# bontor_mbed_lowpan_rev_h.net
KiCad netlist of a schematic drawn in EAGLE
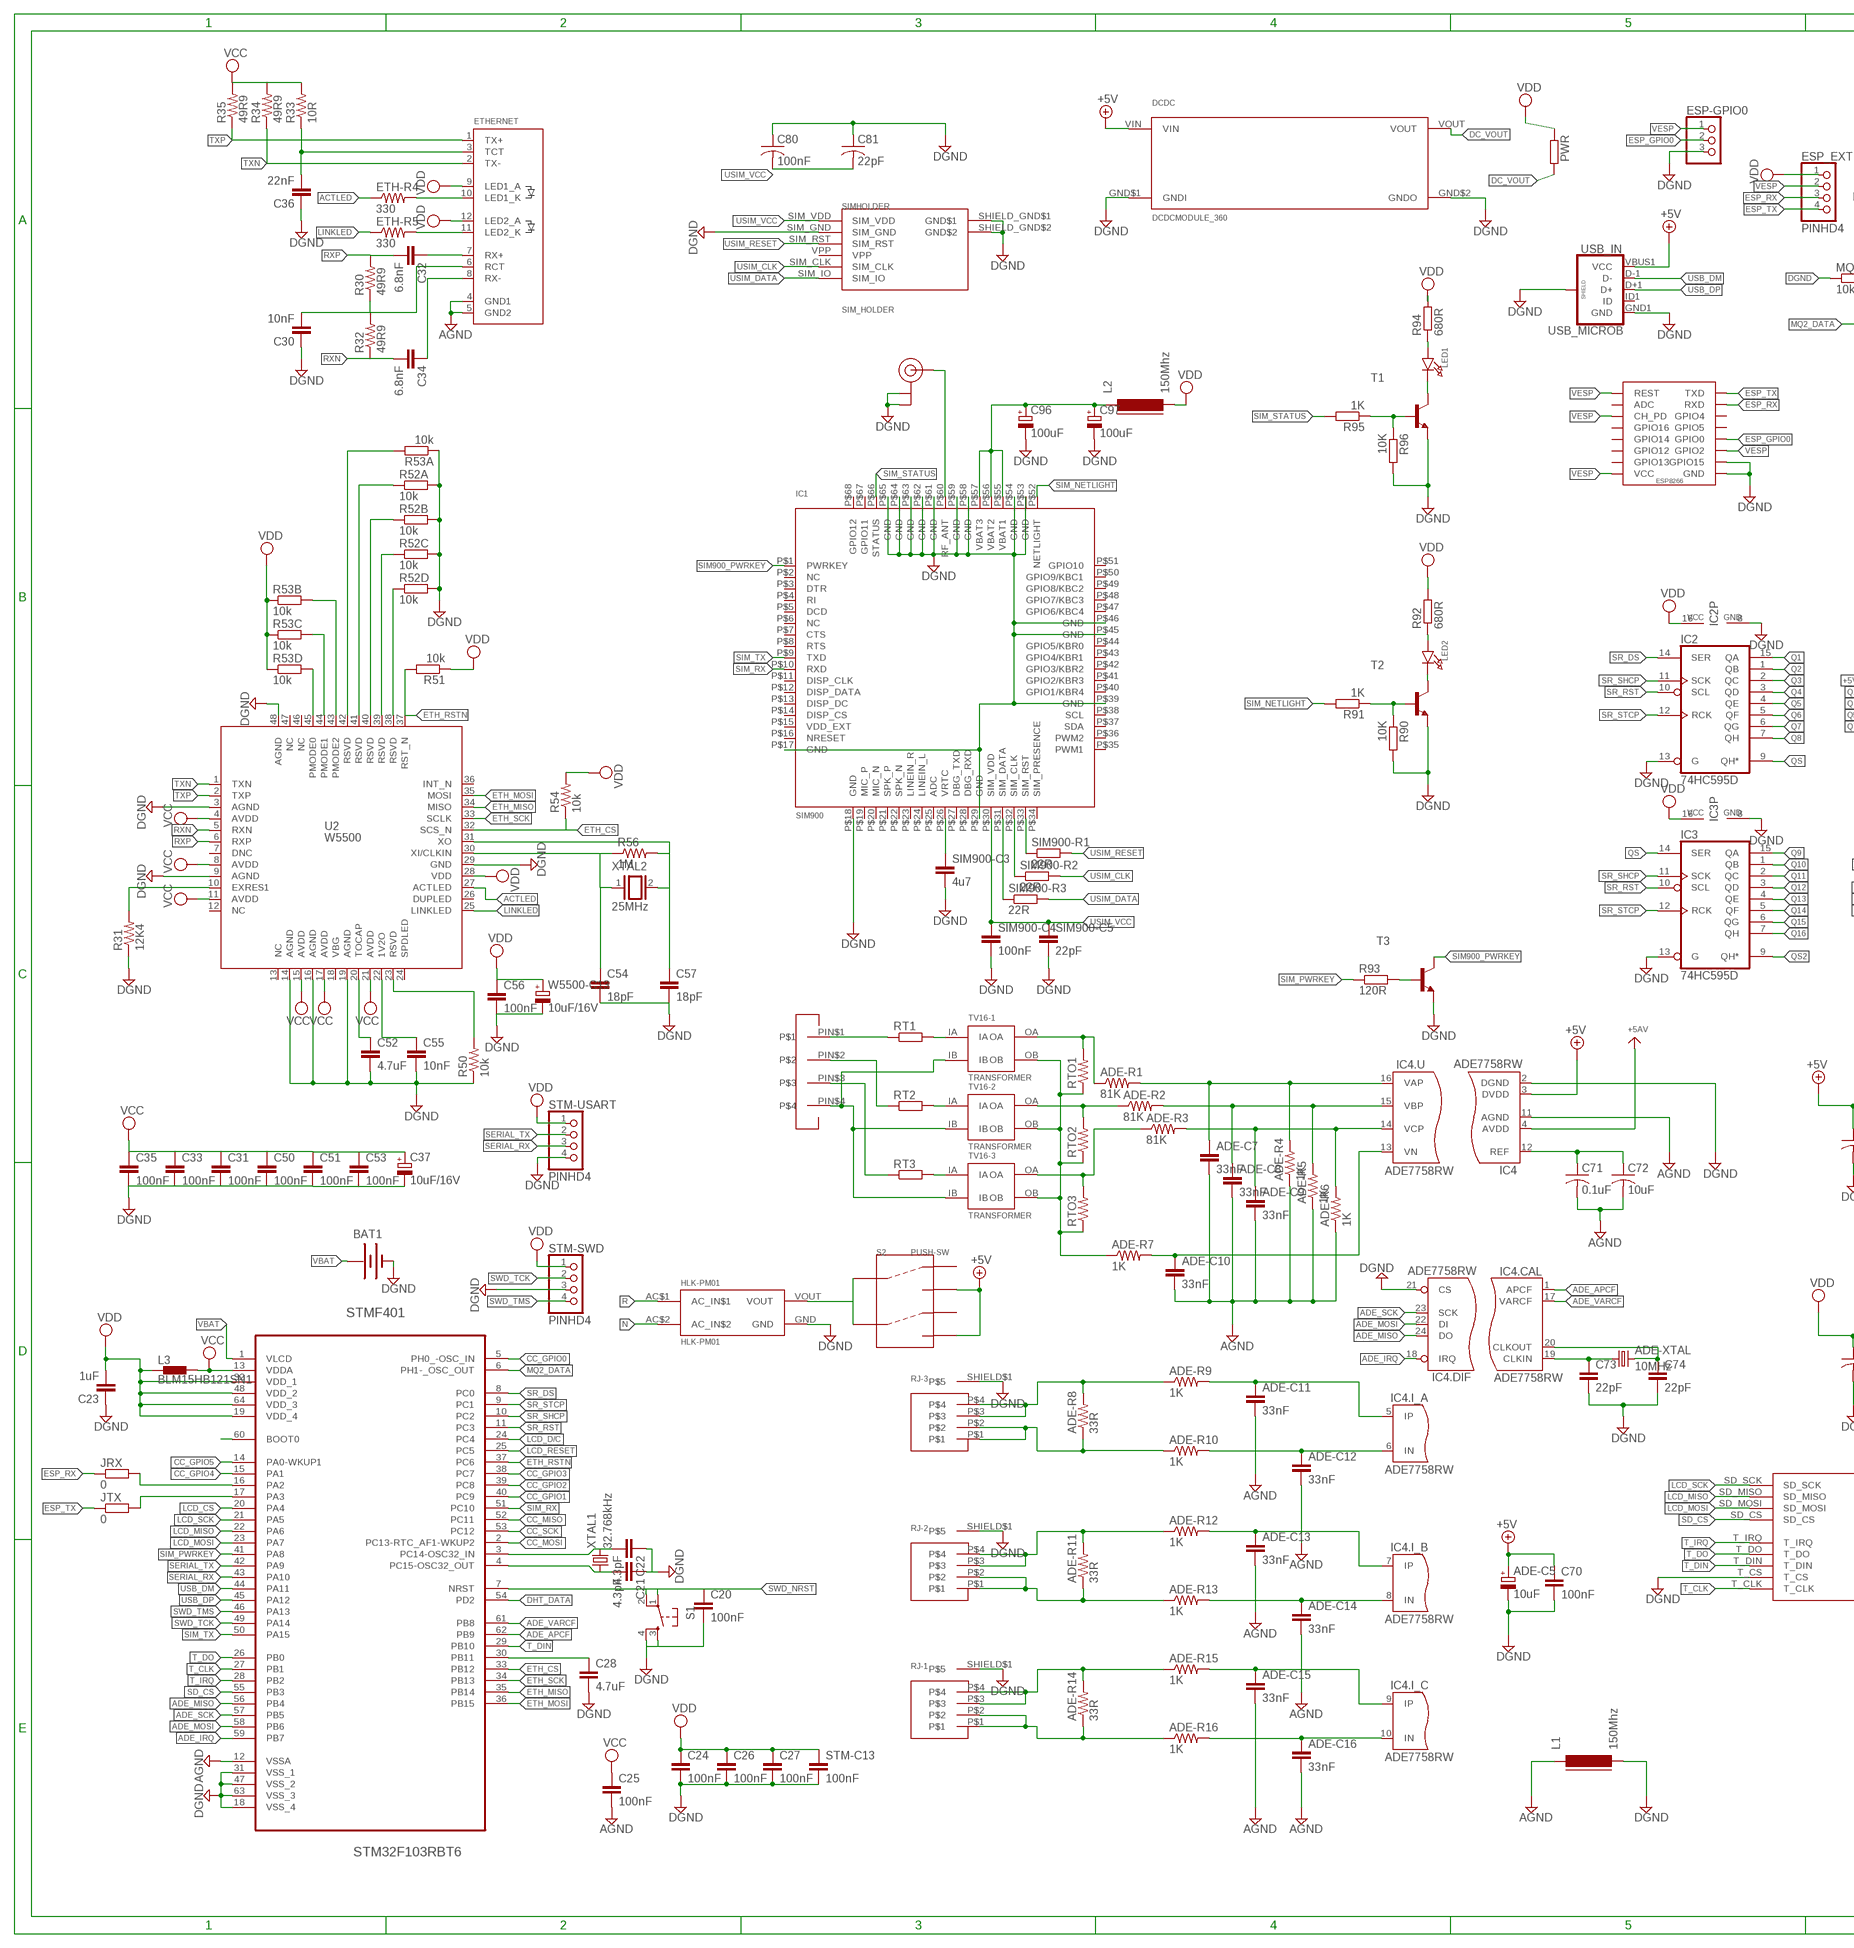
[diagram p0: schematic, sheet 1, part 1 of 2]
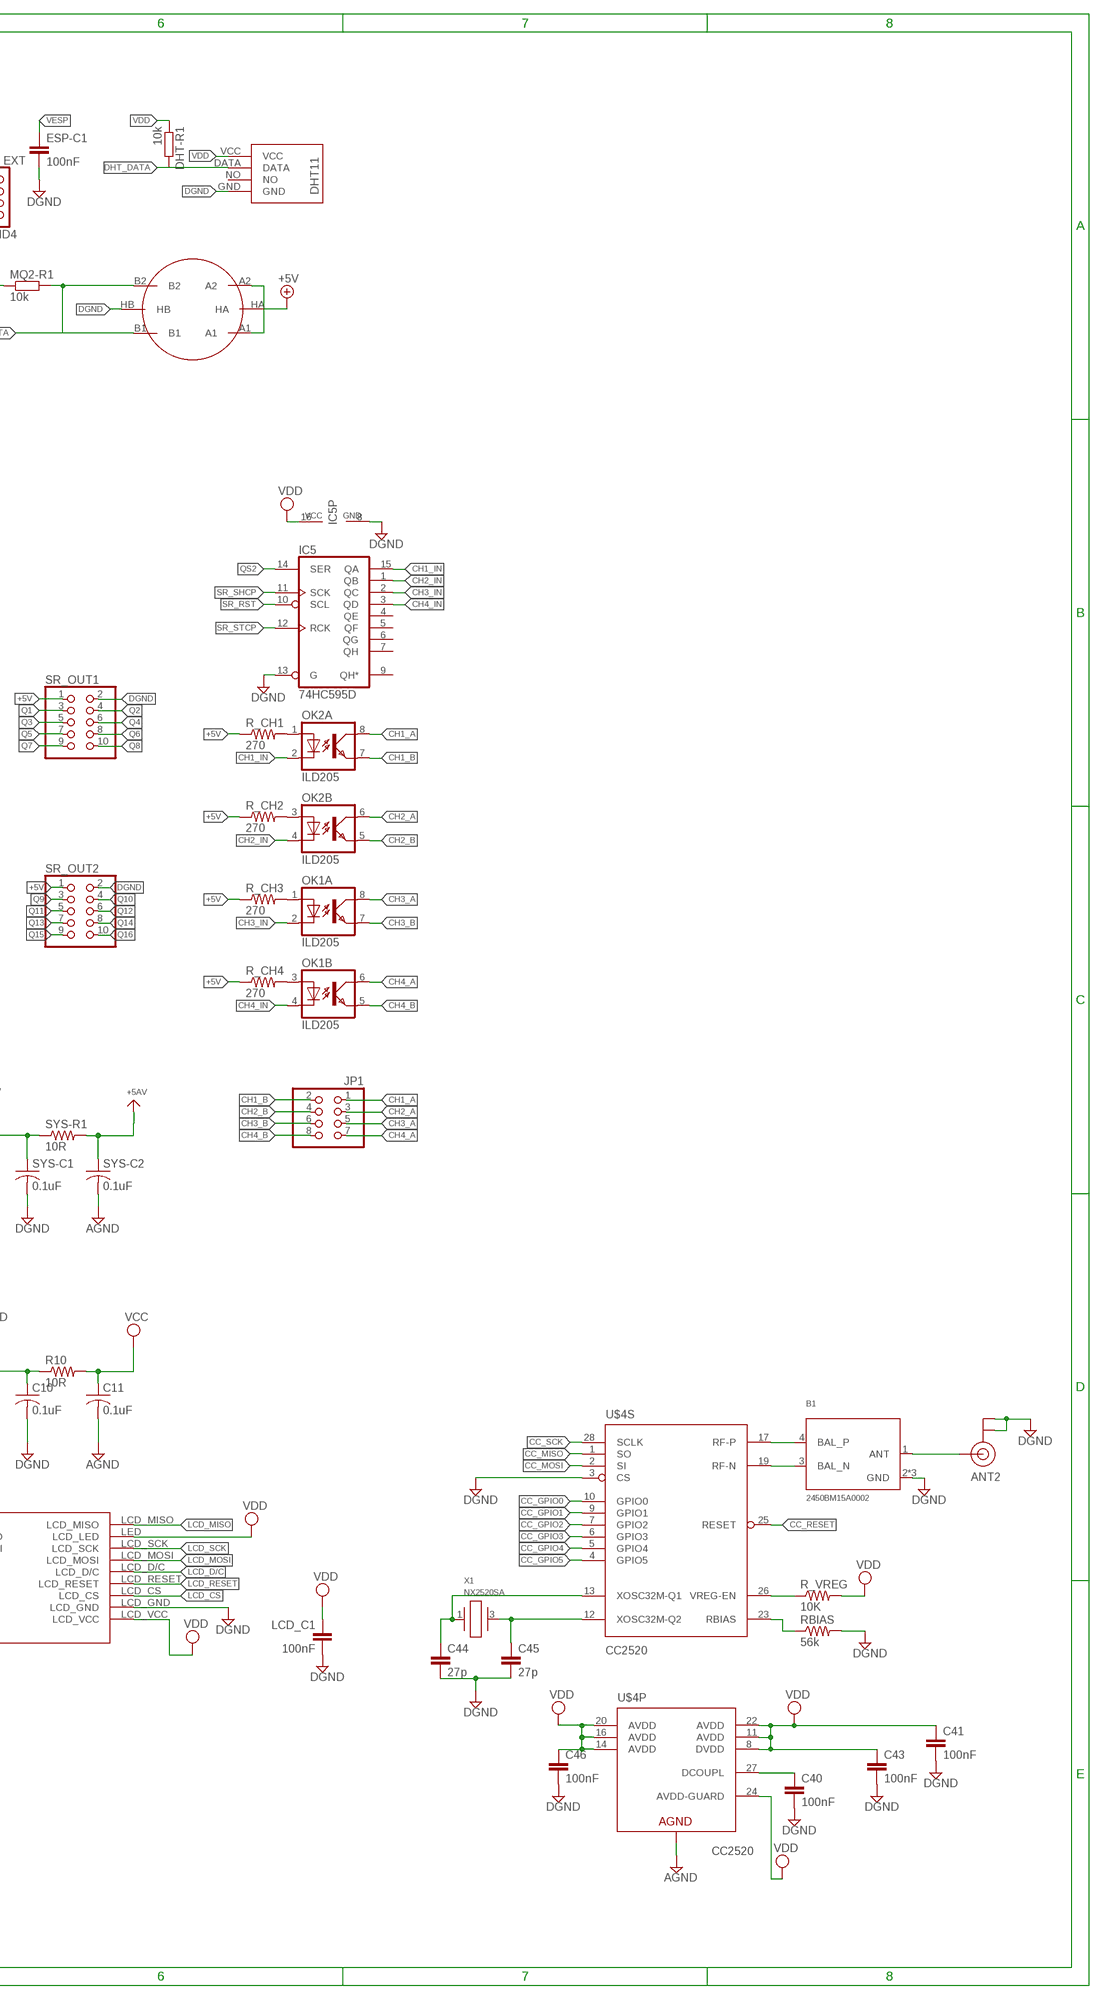
[diagram p1: schematic, sheet 1, part 2 of 2]

(export (version "E")
  (design (tool "Eeschema 10.0.6"))
  (components
    (comp (ref "ADE-C5")
      (value "10uF")
      (footprint "eagle-import:153CLV-0605")
      (libsource (lib "eagle-import") (part "CPOL-EU153CLV-0605"))
    )
    (comp (ref "ADE-C7")
      (value "33nF")
      (footprint "eagle-import:0603-CAP")
      (libsource (lib "eagle-import") (part "CAP0603-CAP"))
    )
    (comp (ref "ADE-C8")
      (value "33nF")
      (footprint "eagle-import:0603-CAP")
      (libsource (lib "eagle-import") (part "CAP0603-CAP"))
    )
    (comp (ref "ADE-C9")
      (value "33nF")
      (footprint "eagle-import:0603-CAP")
      (libsource (lib "eagle-import") (part "CAP0603-CAP"))
    )
    (comp (ref "ADE-C10")
      (value "33nF")
      (footprint "eagle-import:0603-CAP")
      (libsource (lib "eagle-import") (part "CAP0603-CAP"))
    )
    (comp (ref "ADE-C11")
      (value "33nF")
      (footprint "eagle-import:0402-CAP")
      (libsource (lib "eagle-import") (part "CAP0402-CAP"))
    )
    (comp (ref "ADE-C12")
      (value "33nF")
      (footprint "eagle-import:0402-CAP")
      (libsource (lib "eagle-import") (part "CAP0402-CAP"))
    )
    (comp (ref "ADE-C13")
      (value "33nF")
      (footprint "eagle-import:0402-CAP")
      (libsource (lib "eagle-import") (part "CAP0402-CAP"))
    )
    (comp (ref "ADE-C14")
      (value "33nF")
      (footprint "eagle-import:0402-CAP")
      (libsource (lib "eagle-import") (part "CAP0402-CAP"))
    )
    (comp (ref "ADE-C15")
      (value "33nF")
      (footprint "eagle-import:0402-CAP")
      (libsource (lib "eagle-import") (part "CAP0402-CAP"))
    )
    (comp (ref "ADE-C16")
      (value "33nF")
      (footprint "eagle-import:0402-CAP")
      (libsource (lib "eagle-import") (part "CAP0402-CAP"))
    )
    (comp (ref "ADE-R1")
      (value "81K")
      (footprint "eagle-import:0603-RES")
      (libsource (lib "eagle-import") (part "RESISTOR0603-RES"))
    )
    (comp (ref "ADE-R2")
      (value "81K")
      (footprint "eagle-import:0603-RES")
      (libsource (lib "eagle-import") (part "RESISTOR0603-RES"))
    )
    (comp (ref "ADE-R3")
      (value "81K")
      (footprint "eagle-import:0603-RES")
      (libsource (lib "eagle-import") (part "RESISTOR0603-RES"))
    )
    (comp (ref "ADE-R4")
      (value "1K")
      (footprint "eagle-import:0603-RES")
      (libsource (lib "eagle-import") (part "RESISTOR0603-RES"))
    )
    (comp (ref "ADE-R5")
      (value "1K")
      (footprint "eagle-import:0603-RES")
      (libsource (lib "eagle-import") (part "RESISTOR0603-RES"))
    )
    (comp (ref "ADE-R6")
      (value "1K")
      (footprint "eagle-import:0603-RES")
      (libsource (lib "eagle-import") (part "RESISTOR0603-RES"))
    )
    (comp (ref "ADE-R7")
      (value "1K")
      (footprint "eagle-import:0603-RES")
      (libsource (lib "eagle-import") (part "RESISTOR0603-RES"))
    )
    (comp (ref "ADE-R8")
      (value "33R")
      (footprint "eagle-import:0402-RES")
      (libsource (lib "eagle-import") (part "RESISTOR0402-RES"))
    )
    (comp (ref "ADE-R9")
      (value "1K")
      (footprint "eagle-import:0402-RES")
      (libsource (lib "eagle-import") (part "RESISTOR0402-RES"))
    )
    (comp (ref "ADE-R10")
      (value "1K")
      (footprint "eagle-import:0402-RES")
      (libsource (lib "eagle-import") (part "RESISTOR0402-RES"))
    )
    (comp (ref "ADE-R11")
      (value "33R")
      (footprint "eagle-import:0402-RES")
      (libsource (lib "eagle-import") (part "RESISTOR0402-RES"))
    )
    (comp (ref "ADE-R12")
      (value "1K")
      (footprint "eagle-import:0402-RES")
      (libsource (lib "eagle-import") (part "RESISTOR0402-RES"))
    )
    (comp (ref "ADE-R13")
      (value "1K")
      (footprint "eagle-import:0402-RES")
      (libsource (lib "eagle-import") (part "RESISTOR0402-RES"))
    )
    (comp (ref "ADE-R14")
      (value "33R")
      (footprint "eagle-import:0402-RES")
      (libsource (lib "eagle-import") (part "RESISTOR0402-RES"))
    )
    (comp (ref "ADE-R15")
      (value "1K")
      (footprint "eagle-import:0402-RES")
      (libsource (lib "eagle-import") (part "RESISTOR0402-RES"))
    )
    (comp (ref "ADE-R16")
      (value "1K")
      (footprint "eagle-import:0402-RES")
      (libsource (lib "eagle-import") (part "RESISTOR0402-RES"))
    )
    (comp (ref "ADE-XTAL")
      (value "10MHz")
      (footprint "eagle-import:HC49US")
      (libsource (lib "eagle-import") (part "CRYSTALHC49US"))
    )
    (comp (ref "ANT1")
      (value "U.FL")
      (footprint "eagle-import:U.FL")
      (libsource (lib "eagle-import") (part "U.FL"))
    )
    (comp (ref "ANT2")
      (value "U.FL")
      (footprint "eagle-import:U.FL")
      (libsource (lib "eagle-import") (part "SparkFun-Connectors_U.FL"))
    )
    (comp (ref "B1")
      (value "2450BM15A0002")
      (footprint "eagle-import:2450BM")
      (libsource (lib "eagle-import") (part "2450BM15A0002"))
    )
    (comp (ref "BAT1")
      (value "BATTERY12MM")
      (footprint "eagle-import:BATTCON_12MM")
      (libsource (lib "eagle-import") (part "BATTERY12MM"))
    )
    (comp (ref "C10")
      (value "0.1uF")
      (footprint "eagle-import:C0603")
      (libsource (lib "eagle-import") (part "C-USC0603"))
    )
    (comp (ref "C11")
      (value "0.1uF")
      (footprint "eagle-import:C0603")
      (libsource (lib "eagle-import") (part "C-USC0603"))
    )
    (comp (ref "C20")
      (value "100nF")
      (footprint "eagle-import:C0603")
      (libsource (lib "eagle-import") (part "C-EUC0603"))
    )
    (comp (ref "C21")
      (value "4.3pF")
      (footprint "eagle-import:C0603")
      (libsource (lib "eagle-import") (part "C-EUC0603"))
    )
    (comp (ref "C22")
      (value "4.3pF")
      (footprint "eagle-import:C0603")
      (libsource (lib "eagle-import") (part "C-EUC0603"))
    )
    (comp (ref "C23")
      (value "1uF")
      (footprint "eagle-import:C0603")
      (libsource (lib "eagle-import") (part "C-EUC0603"))
    )
    (comp (ref "C24")
      (value "100nF")
      (footprint "eagle-import:C0603")
      (libsource (lib "eagle-import") (part "C-EUC0603"))
    )
    (comp (ref "C25")
      (value "100nF")
      (footprint "eagle-import:C0603")
      (libsource (lib "eagle-import") (part "C-EUC0603"))
    )
    (comp (ref "C26")
      (value "100nF")
      (footprint "eagle-import:C0603")
      (libsource (lib "eagle-import") (part "C-EUC0603"))
    )
    (comp (ref "C27")
      (value "100nF")
      (footprint "eagle-import:C0402")
      (libsource (lib "eagle-import") (part "C-EUC0402"))
    )
    (comp (ref "C28")
      (value "4.7uF")
      (footprint "eagle-import:C0603")
      (libsource (lib "eagle-import") (part "C-EUC0603"))
    )
    (comp (ref "C30")
      (value "10nF")
      (footprint "eagle-import:C0603")
      (libsource (lib "eagle-import") (part "C-EUC0603"))
    )
    (comp (ref "C31")
      (value "100nF")
      (footprint "eagle-import:C0603")
      (libsource (lib "eagle-import") (part "C-EUC0603"))
    )
    (comp (ref "C32")
      (value "6.8nF")
      (footprint "eagle-import:C0603")
      (libsource (lib "eagle-import") (part "C-EUC0603"))
    )
    (comp (ref "C33")
      (value "100nF")
      (footprint "eagle-import:C0603")
      (libsource (lib "eagle-import") (part "C-EUC0603"))
    )
    (comp (ref "C34")
      (value "6.8nF")
      (footprint "eagle-import:C0603")
      (libsource (lib "eagle-import") (part "C-EUC0603"))
    )
    (comp (ref "C35")
      (value "100nF")
      (footprint "eagle-import:C0603")
      (libsource (lib "eagle-import") (part "C-EUC0603"))
    )
    (comp (ref "C36")
      (value "22nF")
      (footprint "eagle-import:C0603")
      (libsource (lib "eagle-import") (part "C-EUC0603"))
    )
    (comp (ref "C37")
      (value "10uF/16V")
      (footprint "eagle-import:153CLV-0605")
      (libsource (lib "eagle-import") (part "CPOL-EU153CLV-0605"))
    )
    (comp (ref "C40")
      (value "100nF")
      (footprint "eagle-import:C0402")
      (libsource (lib "eagle-import") (part "C-EUC0402"))
    )
    (comp (ref "C41")
      (value "100nF")
      (footprint "eagle-import:C0402")
      (libsource (lib "eagle-import") (part "C-EUC0402"))
    )
    (comp (ref "C43")
      (value "100nF")
      (footprint "eagle-import:C0402")
      (libsource (lib "eagle-import") (part "C-EUC0402"))
    )
    (comp (ref "C44")
      (value "27p")
      (footprint "eagle-import:C0201")
      (libsource (lib "eagle-import") (part "C-EUC0201"))
    )
    (comp (ref "C45")
      (value "27p")
      (footprint "eagle-import:C0201")
      (libsource (lib "eagle-import") (part "C-EUC0201"))
    )
    (comp (ref "C46")
      (value "100nF")
      (footprint "eagle-import:C0402")
      (libsource (lib "eagle-import") (part "C-EUC0402"))
    )
    (comp (ref "C50")
      (value "100nF")
      (footprint "eagle-import:C0603")
      (libsource (lib "eagle-import") (part "C-EUC0603"))
    )
    (comp (ref "C51")
      (value "100nF")
      (footprint "eagle-import:C0603")
      (libsource (lib "eagle-import") (part "C-EUC0603"))
    )
    (comp (ref "C52")
      (value "4.7uF")
      (footprint "eagle-import:C0603")
      (libsource (lib "eagle-import") (part "C-EUC0603"))
    )
    (comp (ref "C53")
      (value "100nF")
      (footprint "eagle-import:C0603")
      (libsource (lib "eagle-import") (part "C-EUC0603"))
    )
    (comp (ref "C54")
      (value "18pF")
      (footprint "eagle-import:C0603")
      (libsource (lib "eagle-import") (part "C-EUC0603"))
    )
    (comp (ref "C55")
      (value "10nF")
      (footprint "eagle-import:C0603")
      (libsource (lib "eagle-import") (part "C-EUC0603"))
    )
    (comp (ref "C56")
      (value "100nF")
      (footprint "eagle-import:C0603")
      (libsource (lib "eagle-import") (part "C-EUC0603"))
    )
    (comp (ref "C57")
      (value "18pF")
      (footprint "eagle-import:C0603")
      (libsource (lib "eagle-import") (part "C-EUC0603"))
    )
    (comp (ref "C70")
      (value "100nF")
      (footprint "eagle-import:C0603")
      (libsource (lib "eagle-import") (part "C-EUC0603"))
    )
    (comp (ref "C71")
      (value "0.1uF")
      (footprint "eagle-import:C0603")
      (libsource (lib "eagle-import") (part "C-USC0603"))
    )
    (comp (ref "C72")
      (value "10uF")
      (footprint "eagle-import:C0805K")
      (libsource (lib "eagle-import") (part "C-USC0805K"))
    )
    (comp (ref "C73")
      (value "22pF")
      (footprint "eagle-import:C0603")
      (libsource (lib "eagle-import") (part "C-EUC0603"))
    )
    (comp (ref "C74")
      (value "22pF")
      (footprint "eagle-import:C0603")
      (libsource (lib "eagle-import") (part "C-EUC0603"))
    )
    (comp (ref "C80")
      (value "100nF")
      (footprint "eagle-import:C0603K")
      (libsource (lib "eagle-import") (part "C-USC0603K"))
    )
    (comp (ref "C81")
      (value "22pF")
      (footprint "eagle-import:C0603K")
      (libsource (lib "eagle-import") (part "C-USC0603K"))
    )
    (comp (ref "C96")
      (value "100uF")
      (footprint "eagle-import:153CLV-0605")
      (libsource (lib "eagle-import") (part "CPOL-EU153CLV-0605"))
    )
    (comp (ref "C97")
      (value "100uF")
      (footprint "eagle-import:153CLV-0605")
      (libsource (lib "eagle-import") (part "CPOL-EU153CLV-0605"))
    )
    (comp (ref "DCDC")
      (value "DCDCMODULE_360")
      (footprint "eagle-import:DCDCMODULE-360")
      (libsource (lib "eagle-import") (part "DCDCMODULE_360"))
    )
    (comp (ref "DHT-R1")
      (value "10k")
      (footprint "eagle-import:R0603")
      (libsource (lib "eagle-import") (part "resistor_R-EU_R0603"))
    )
    (comp (ref "ESP")
      (value "ESP")
      (footprint "eagle-import:WI12")
      (libsource (lib "eagle-import") (part "ESP8266WI12"))
    )
    (comp (ref "ESP-C1")
      (value "100nF")
      (footprint "eagle-import:C0603")
      (libsource (lib "eagle-import") (part "C-EUC0603"))
    )
    (comp (ref "ESP-GPIO0")
      (value "PINHD-1X3")
      (footprint "eagle-import:1X03")
      (libsource (lib "eagle-import") (part "PINHD-1X3"))
    )
    (comp (ref "ESP_EXT")
      (value "PINHD4")
      (footprint "eagle-import:PINHD4")
      (libsource (lib "eagle-import") (part "PINHD4"))
    )
    (comp (ref "ETH-R4")
      (value "330")
      (footprint "eagle-import:R0603")
      (libsource (lib "eagle-import") (part "resistor_R-US_R0603"))
    )
    (comp (ref "ETH-R5")
      (value "330")
      (footprint "eagle-import:R0603")
      (libsource (lib "eagle-import") (part "resistor_R-US_R0603"))
    )
    (comp (ref "ETHERNET")
      (value "RJ45J0026D21BNL")
      (footprint "eagle-import:RJ45_PULSEJACK")
      (libsource (lib "eagle-import") (part "RJ45J0026D21BNL"))
    )
    (comp (ref "HLK-PM01")
      (value "HLK-PM01")
      (footprint "eagle-import:HLK-PM01")
      (libsource (lib "eagle-import") (part "HLK-PM01"))
    )
    (comp (ref "IC1")
      (value "SIM900")
      (footprint "eagle-import:SIM900_SMT")
      (libsource (lib "eagle-import") (part "GSM_SIM900_LITERAL"))
    )
    (comp (ref "IC2")
      (value "74HC595D")
      (footprint "eagle-import:SO16")
      (libsource (lib "eagle-import") (part "74595DHC"))
    )
    (comp (ref "IC3")
      (value "74HC595D")
      (footprint "eagle-import:SO16")
      (libsource (lib "eagle-import") (part "74595DHC"))
    )
    (comp (ref "IC4")
      (value "ADE7758RW")
      (footprint "eagle-import:SOIC24")
      (libsource (lib "eagle-import") (part "ADE7758RW"))
    )
    (comp (ref "IC5")
      (value "74HC595D")
      (footprint "eagle-import:SO16")
      (libsource (lib "eagle-import") (part "74595DHC"))
    )
    (comp (ref "JP1")
      (value "PINHD-2X4")
      (footprint "eagle-import:2X04")
      (libsource (lib "eagle-import") (part "PINHD-2X4"))
    )
    (comp (ref "JRX")
      (value "0")
      (footprint "eagle-import:R0603")
      (libsource (lib "eagle-import") (part "R-EU_R0603"))
    )
    (comp (ref "JTX")
      (value "0")
      (footprint "eagle-import:R0603")
      (libsource (lib "eagle-import") (part "R-EU_R0603"))
    )
    (comp (ref "L1")
      (value "150Mhz")
      (footprint "eagle-import:FB805")
      (libsource (lib "eagle-import") (part "FERRITE-0805"))
    )
    (comp (ref "L2")
      (value "150Mhz")
      (footprint "eagle-import:FB805")
      (libsource (lib "eagle-import") (part "FERRITE-0805"))
    )
    (comp (ref "L3")
      (value "BLM15HB121SN1")
      (footprint "eagle-import:0402")
      (libsource (lib "eagle-import") (part "BLM15HB121SN1"))
    )
    (comp (ref "LCD14")
      (value "LCD_2.4")
      (footprint "eagle-import:LCD_TOUCH_2-4")
      (libsource (lib "eagle-import") (part "LCD_2.4"))
    )
    (comp (ref "LCD_C1")
      (value "100nF")
      (footprint "eagle-import:C0603")
      (libsource (lib "eagle-import") (part "C-EUC0603"))
    )
    (comp (ref "LED1")
      (value "LED0805_NOOUTLINE")
      (footprint "eagle-import:CHIPLED_0805_NOOUTLINE")
      (libsource (lib "eagle-import") (part "LED0805_NOOUTLINE"))
    )
    (comp (ref "LED2")
      (value "LED0805_NOOUTLINE")
      (footprint "eagle-import:CHIPLED_0805_NOOUTLINE")
      (libsource (lib "eagle-import") (part "LED0805_NOOUTLINE"))
    )
    (comp (ref "MQ2-R1")
      (value "10k")
      (footprint "eagle-import:R0603")
      (libsource (lib "eagle-import") (part "resistor_R-EU_R0603"))
    )
    (comp (ref "OK1")
      (value "ILD205")
      (footprint "eagle-import:SOIC08")
      (fields (field (name "MF") "VISHAY/TELEFUNKEN") (field (name "MPN") "ILD205T"))
      (libsource (lib "eagle-import") (part "ILD205"))
    )
    (comp (ref "OK2")
      (value "ILD205")
      (footprint "eagle-import:SOIC08")
      (fields (field (name "MF") "VISHAY/TELEFUNKEN") (field (name "MPN") "ILD205T"))
      (libsource (lib "eagle-import") (part "ILD205"))
    )
    (comp (ref "PWR")
      (value "R-EU_R0805")
      (footprint "eagle-import:R0805")
      (libsource (lib "eagle-import") (part "R-EU_R0805"))
    )
    (comp (ref "R10")
      (value "10R")
      (footprint "eagle-import:0603-RES")
      (libsource (lib "eagle-import") (part "RESISTOR0603-RES"))
    )
    (comp (ref "R30")
      (value "49R9")
      (footprint "eagle-import:R0603")
      (libsource (lib "eagle-import") (part "resistor_R-US_R0603"))
    )
    (comp (ref "R31")
      (value "12K4")
      (footprint "eagle-import:R0805")
      (libsource (lib "eagle-import") (part "resistor_R-US_R0805"))
    )
    (comp (ref "R32")
      (value "49R9")
      (footprint "eagle-import:R0603")
      (libsource (lib "eagle-import") (part "resistor_R-US_R0603"))
    )
    (comp (ref "R33")
      (value "10R")
      (footprint "eagle-import:R0603")
      (libsource (lib "eagle-import") (part "resistor_R-US_R0603"))
    )
    (comp (ref "R34")
      (value "49R9")
      (footprint "eagle-import:R0603")
      (libsource (lib "eagle-import") (part "resistor_R-US_R0603"))
    )
    (comp (ref "R35")
      (value "49R9")
      (footprint "eagle-import:R0603")
      (libsource (lib "eagle-import") (part "resistor_R-US_R0603"))
    )
    (comp (ref "R50")
      (value "10k")
      (footprint "eagle-import:R0603")
      (libsource (lib "eagle-import") (part "resistor_R-US_R0603"))
    )
    (comp (ref "R51")
      (value "10k")
      (footprint "eagle-import:R0603")
      (libsource (lib "eagle-import") (part "R-EU_R0603"))
    )
    (comp (ref "R52")
      (value "10k")
      (footprint "eagle-import:RN8P-4R-CRA06S")
      (libsource (lib "eagle-import") (part "RESISTOR_ARRAY_4"))
    )
    (comp (ref "R53")
      (value "10k")
      (footprint "eagle-import:RN8P-4R-CRA06S")
      (libsource (lib "eagle-import") (part "RESISTOR_ARRAY_4"))
    )
    (comp (ref "R54")
      (value "10k")
      (footprint "eagle-import:R0603")
      (libsource (lib "eagle-import") (part "resistor_R-US_R0603"))
    )
    (comp (ref "R56")
      (value "1M")
      (footprint "eagle-import:R0603")
      (libsource (lib "eagle-import") (part "resistor_R-US_R0603"))
    )
    (comp (ref "R90")
      (value "10K")
      (footprint "eagle-import:R0603")
      (libsource (lib "eagle-import") (part "R-EU_R0603"))
    )
    (comp (ref "R91")
      (value "1K")
      (footprint "eagle-import:R0603")
      (libsource (lib "eagle-import") (part "R-EU_R0603"))
    )
    (comp (ref "R92")
      (value "680R")
      (footprint "eagle-import:R0603")
      (libsource (lib "eagle-import") (part "R-EU_R0603"))
    )
    (comp (ref "R93")
      (value "120R")
      (footprint "eagle-import:R0603")
      (libsource (lib "eagle-import") (part "resistor_R-EU_R0603"))
    )
    (comp (ref "R94")
      (value "680R")
      (footprint "eagle-import:R0603")
      (libsource (lib "eagle-import") (part "R-EU_R0603"))
    )
    (comp (ref "R95")
      (value "1K")
      (footprint "eagle-import:R0603")
      (libsource (lib "eagle-import") (part "R-EU_R0603"))
    )
    (comp (ref "R96")
      (value "10K")
      (footprint "eagle-import:R0603")
      (libsource (lib "eagle-import") (part "R-EU_R0603"))
    )
    (comp (ref "RBIAS")
      (value "56k")
      (footprint "eagle-import:0402-RES")
      (libsource (lib "eagle-import") (part "RESISTOR0402-RES"))
    )
    (comp (ref "RJ-1")
      (value "RJ11-4P-V")
      (footprint "eagle-import:RJ11-4P-V")
      (libsource (lib "eagle-import") (part "RJ11-4P-V"))
    )
    (comp (ref "RJ-2")
      (value "RJ11-4P-V")
      (footprint "eagle-import:RJ11-4P-V")
      (libsource (lib "eagle-import") (part "RJ11-4P-V"))
    )
    (comp (ref "RJ-3")
      (value "RJ11-4P-V")
      (footprint "eagle-import:RJ11-4P-V")
      (libsource (lib "eagle-import") (part "RJ11-4P-V"))
    )
    (comp (ref "RT1")
      (value "R-EU_0309/V")
      (footprint "eagle-import:0309V")
      (libsource (lib "eagle-import") (part "R-EU_0309/V"))
    )
    (comp (ref "RT2")
      (value "R-EU_0309/V")
      (footprint "eagle-import:0309V")
      (libsource (lib "eagle-import") (part "R-EU_0309/V"))
    )
    (comp (ref "RT3")
      (value "R-EU_0309/V")
      (footprint "eagle-import:0309V")
      (libsource (lib "eagle-import") (part "R-EU_0309/V"))
    )
    (comp (ref "RTO1")
      (value "R-US_0309_12")
      (footprint "eagle-import:0309_12")
      (libsource (lib "eagle-import") (part "R-US_0309_12"))
    )
    (comp (ref "RTO2")
      (value "R-US_0309_12")
      (footprint "eagle-import:0309_12")
      (libsource (lib "eagle-import") (part "R-US_0309_12"))
    )
    (comp (ref "RTO3")
      (value "R-US_0309_12")
      (footprint "eagle-import:0309_12")
      (libsource (lib "eagle-import") (part "R-US_0309_12"))
    )
    (comp (ref "R_CH1")
      (value "270")
      (footprint "eagle-import:0603-RES")
      (libsource (lib "eagle-import") (part "RESISTOR0603-RES"))
    )
    (comp (ref "R_CH2")
      (value "270")
      (footprint "eagle-import:0603-RES")
      (libsource (lib "eagle-import") (part "RESISTOR0603-RES"))
    )
    (comp (ref "R_CH3")
      (value "270")
      (footprint "eagle-import:0603-RES")
      (libsource (lib "eagle-import") (part "RESISTOR0603-RES"))
    )
    (comp (ref "R_CH4")
      (value "270")
      (footprint "eagle-import:0603-RES")
      (libsource (lib "eagle-import") (part "RESISTOR0603-RES"))
    )
    (comp (ref "R_VREG")
      (value "10K")
      (footprint "eagle-import:0402-RES")
      (libsource (lib "eagle-import") (part "RESISTOR0402-RES"))
    )
    (comp (ref "S1")
      (value "TAC_SWITCHPTH")
      (footprint "eagle-import:TACTILE-PTH")
      (libsource (lib "eagle-import") (part "TAC_SWITCHPTH"))
    )
    (comp (ref "S2")
      (value "PUSH-SW")
      (footprint "eagle-import:SWITCH-6PIN-LOCK-2.54MM")
      (libsource (lib "eagle-import") (part "SWITCH-6PIN-LOCK-2.54MM"))
    )
    (comp (ref "SENSOR-MQ2")
      (value "METHANE_SENSOR")
      (footprint "eagle-import:MQ-3")
      (libsource (lib "eagle-import") (part "METHANE_SENSOR"))
    )
    (comp (ref "SIM900-C3")
      (value "4u7")
      (footprint "eagle-import:C0603")
      (libsource (lib "eagle-import") (part "C-EUC0603"))
    )
    (comp (ref "SIM900-C4")
      (value "100nF")
      (footprint "eagle-import:C0603")
      (libsource (lib "eagle-import") (part "C-EUC0603"))
    )
    (comp (ref "SIM900-C5")
      (value "22pF")
      (footprint "eagle-import:C0603")
      (libsource (lib "eagle-import") (part "C-EUC0603"))
    )
    (comp (ref "SIM900-R1")
      (value "22R")
      (footprint "eagle-import:R0603")
      (libsource (lib "eagle-import") (part "R-EU_R0603"))
    )
    (comp (ref "SIM900-R2")
      (value "22R")
      (footprint "eagle-import:R0603")
      (libsource (lib "eagle-import") (part "R-EU_R0603"))
    )
    (comp (ref "SIM900-R3")
      (value "22R")
      (footprint "eagle-import:R0603")
      (libsource (lib "eagle-import") (part "R-EU_R0603"))
    )
    (comp (ref "SIMHOLDER")
      (value "SIM_HOLDER")
      (footprint "eagle-import:SIMHOLDER-PUSHPUSH")
      (libsource (lib "eagle-import") (part "SIM_HOLDER"))
    )
    (comp (ref "SR_OUT1")
      (value "PINHD-2X5")
      (footprint "eagle-import:2X05")
      (libsource (lib "eagle-import") (part "PINHD-2X5"))
    )
    (comp (ref "SR_OUT2")
      (value "PINHD-2X5")
      (footprint "eagle-import:2X05")
      (libsource (lib "eagle-import") (part "PINHD-2X5"))
    )
    (comp (ref "STM-C13")
      (value "100nF")
      (footprint "eagle-import:C0603")
      (libsource (lib "eagle-import") (part "C-EUC0603"))
    )
    (comp (ref "STM-SWD")
      (value "PINHD4")
      (footprint "eagle-import:PINHD4")
      (libsource (lib "eagle-import") (part "PINHD4"))
    )
    (comp (ref "STM-USART")
      (value "PINHD4")
      (footprint "eagle-import:PINHD4")
      (libsource (lib "eagle-import") (part "PINHD4"))
    )
    (comp (ref "STMF401")
      (value "STM32F103RBT6")
      (footprint "eagle-import:QFP50P1200X1200X160-64N")
      (fields (field (name "MPN") "STM32L152RBT6"))
      (libsource (lib "eagle-import") (part "STM32L152RBT6"))
    )
    (comp (ref "SYS-C1")
      (value "0.1uF")
      (footprint "eagle-import:C0603")
      (libsource (lib "eagle-import") (part "C-USC0603"))
    )
    (comp (ref "SYS-C2")
      (value "0.1uF")
      (footprint "eagle-import:C0603")
      (libsource (lib "eagle-import") (part "C-USC0603"))
    )
    (comp (ref "SYS-R1")
      (value "10R")
      (footprint "eagle-import:0603-RES")
      (libsource (lib "eagle-import") (part "RESISTOR0603-RES"))
    )
    (comp (ref "T1")
      (value "MMBT2222ALT1-NPN-SOT23-BEC")
      (footprint "eagle-import:SOT23-BEC")
      (libsource (lib "eagle-import") (part "-NPN-SOT23-BECMMBT2222ALT1"))
    )
    (comp (ref "T2")
      (value "MMBT2222ALT1-NPN-SOT23-BEC")
      (footprint "eagle-import:SOT23-BEC")
      (libsource (lib "eagle-import") (part "-NPN-SOT23-BECMMBT2222ALT1"))
    )
    (comp (ref "T3")
      (value "MMBT2222ALT1-NPN-SOT23-BEC")
      (footprint "eagle-import:SOT23-BEC")
      (libsource (lib "eagle-import") (part "transistor-neu-to92_-NPN-SOT23-BECMMBT2222ALT1"))
    )
    (comp (ref "TERM_BLOCK")
      (value "TERMINAL_BLOCK_TW")
      (footprint "eagle-import:TERMINAL-TWO-WAY")
      (libsource (lib "eagle-import") (part "TERMINAL_BLOCK_TW"))
    )
    (comp (ref "TV16-1")
      (value "TRANSFORMER")
      (footprint "eagle-import:TV16")
      (libsource (lib "eagle-import") (part "TRANSFORMER"))
    )
    (comp (ref "TV16-2")
      (value "TRANSFORMER")
      (footprint "eagle-import:TV16")
      (libsource (lib "eagle-import") (part "TRANSFORMER"))
    )
    (comp (ref "TV16-3")
      (value "TRANSFORMER")
      (footprint "eagle-import:TV16")
      (libsource (lib "eagle-import") (part "TRANSFORMER"))
    )
    (comp (ref "U$4")
      (value "CC2520")
      (footprint "eagle-import:QFN50P500X500X100-29N")
      (libsource (lib "eagle-import") (part "CC2520"))
    )
    (comp (ref "U$17")
      (value "DHT11")
      (footprint "eagle-import:DHT11")
      (libsource (lib "eagle-import") (part "DHT11"))
    )
    (comp (ref "U2")
      (value "W5500")
      (footprint "eagle-import:W5500")
      (libsource (lib "eagle-import") (part "W5500"))
    )
    (comp (ref "USB_IN")
      (value "USB_MICROB")
      (footprint "eagle-import:USB-B-MICRO-SMD_V03")
      (libsource (lib "eagle-import") (part "USB_MICROB_PLUGCONN-11752"))
    )
    (comp (ref "W5500-C13")
      (value "10uF/16V")
      (footprint "eagle-import:153CLV-0605")
      (libsource (lib "eagle-import") (part "CPOL-EU153CLV-0605"))
    )
    (comp (ref "X1")
      (value "NX2520SA")
      (footprint "eagle-import:NX2520SA")
      (libsource (lib "eagle-import") (part "NX2520SA"))
    )
    (comp (ref "XTAL1")
      (value "32.768kHz")
      (footprint "eagle-import:TC26H")
      (libsource (lib "eagle-import") (part "CRYSTALTC26H"))
    )
    (comp (ref "XTAL2")
      (value "25MHz")
      (footprint "eagle-import:QS")
      (libsource (lib "eagle-import") (part "XTAL/S"))
    )
  )
  (nets
    (net (code "1") (name "+5AV") (class "Default")
      (node (ref "IC4") (pin "4") (pinfunction "AVDD_4") (pintype "power_in"))
      (node (ref "SYS-C2") (pin "1") (pinfunction "1_1") (pintype "passive"))
      (node (ref "SYS-R1") (pin "2") (pinfunction "2_2") (pintype "passive"))
    )
    (net (code "2") (name "+5V") (class "Default")
      (node (ref "ADE-C5") (pin "+") (pinfunction "+_+") (pintype "passive"))
      (node (ref "C70") (pin "1") (pinfunction "1_1") (pintype "passive"))
      (node (ref "DCDC") (pin "VIN") (pinfunction "VIN_VIN") (pintype "bidirectional"))
      (node (ref "IC4") (pin "3") (pinfunction "DVDD_3") (pintype "power_in"))
      (node (ref "R_CH1") (pin "1") (pinfunction "1_1") (pintype "passive"))
      (node (ref "R_CH2") (pin "1") (pinfunction "1_1") (pintype "passive"))
      (node (ref "R_CH3") (pin "1") (pinfunction "1_1") (pintype "passive"))
      (node (ref "R_CH4") (pin "1") (pinfunction "1_1") (pintype "passive"))
      (node (ref "S2") (pin "P$3") (pinfunction "P$3_P$3") (pintype "bidirectional"))
      (node (ref "S2") (pin "P$6") (pinfunction "P$6_P$6") (pintype "bidirectional"))
      (node (ref "SENSOR-MQ2") (pin "A1") (pinfunction "A1_A1") (pintype "bidirectional"))
      (node (ref "SENSOR-MQ2") (pin "A2") (pinfunction "A2_A2") (pintype "bidirectional"))
      (node (ref "SENSOR-MQ2") (pin "HA") (pinfunction "HA_HA") (pintype "bidirectional"))
      (node (ref "SR_OUT1") (pin "1") (pinfunction "1_1") (pintype "passive"))
      (node (ref "SR_OUT2") (pin "1") (pinfunction "1_1") (pintype "passive"))
      (node (ref "SYS-C1") (pin "1") (pinfunction "1_1") (pintype "passive"))
      (node (ref "SYS-R1") (pin "1") (pinfunction "1_1") (pintype "passive"))
      (node (ref "USB_IN") (pin "VBUS1") (pinfunction "VCC_VBUS1") (pintype "bidirectional"))
    )
    (net (code "3") (name "/GPIO11") (class "Default")
      (node (ref "IC1") (pin "P$67") (pinfunction "GPIO11_P$67") (pintype "power_in"))
    )
    (net (code "4") (name "/GPIO12") (class "Default")
      (node (ref "IC1") (pin "P$68") (pinfunction "GPIO12_P$68") (pintype "power_in"))
    )
    (net (code "5") (name "ACTLED") (class "Default")
      (node (ref "ETH-R4") (pin "1") (pinfunction "1_1") (pintype "passive"))
      (node (ref "U2") (pin "27") (pinfunction "ACTLED_27") (pintype "passive"))
    )
    (net (code "6") (name "ADE_APCF") (class "Default")
      (node (ref "IC4") (pin "1") (pinfunction "APCF_1") (pintype "output"))
      (node (ref "STMF401") (pin "62") (pinfunction "PB9_62") (pintype "bidirectional"))
    )
    (net (code "7") (name "ADE_IRQ") (class "Default")
      (node (ref "IC4") (pin "18") (pinfunction "IRQ_18") (pintype "output"))
      (node (ref "STMF401") (pin "59") (pinfunction "PB7_59") (pintype "bidirectional"))
    )
    (net (code "8") (name "ADE_MISO") (class "Default")
      (node (ref "IC4") (pin "24") (pinfunction "DO_24") (pintype "output"))
      (node (ref "STMF401") (pin "56") (pinfunction "PB4_56") (pintype "bidirectional"))
    )
    (net (code "9") (name "ADE_MOSI") (class "Default")
      (node (ref "IC4") (pin "22") (pinfunction "DI_22") (pintype "input"))
      (node (ref "STMF401") (pin "58") (pinfunction "PB6_58") (pintype "bidirectional"))
    )
    (net (code "10") (name "ADE_SCK") (class "Default")
      (node (ref "IC4") (pin "23") (pinfunction "SCK_23") (pintype "input"))
      (node (ref "STMF401") (pin "57") (pinfunction "PB5_57") (pintype "bidirectional"))
    )
    (net (code "11") (name "ADE_VARCF") (class "Default")
      (node (ref "IC4") (pin "17") (pinfunction "VARCF_17") (pintype "output"))
      (node (ref "STMF401") (pin "61") (pinfunction "PB8_61") (pintype "bidirectional"))
    )
    (net (code "12") (name "AGND") (class "Default")
      (node (ref "ADE-C10") (pin "2") (pinfunction "2_2") (pintype "passive"))
      (node (ref "ADE-C11") (pin "2") (pinfunction "2_2") (pintype "passive"))
      (node (ref "ADE-C12") (pin "2") (pinfunction "2_2") (pintype "passive"))
      (node (ref "ADE-C13") (pin "2") (pinfunction "2_2") (pintype "passive"))
      (node (ref "ADE-C14") (pin "2") (pinfunction "2_2") (pintype "passive"))
      (node (ref "ADE-C15") (pin "2") (pinfunction "2_2") (pintype "passive"))
      (node (ref "ADE-C16") (pin "2") (pinfunction "2_2") (pintype "passive"))
      (node (ref "ADE-C7") (pin "2") (pinfunction "2_2") (pintype "passive"))
      (node (ref "ADE-C8") (pin "2") (pinfunction "2_2") (pintype "passive"))
      (node (ref "ADE-C9") (pin "2") (pinfunction "2_2") (pintype "passive"))
      (node (ref "ADE-R4") (pin "1") (pinfunction "1_1") (pintype "passive"))
      (node (ref "ADE-R5") (pin "1") (pinfunction "1_1") (pintype "passive"))
      (node (ref "ADE-R6") (pin "1") (pinfunction "1_1") (pintype "passive"))
      (node (ref "C11") (pin "2") (pinfunction "2_2") (pintype "passive"))
      (node (ref "C25") (pin "2") (pinfunction "2_2") (pintype "passive"))
      (node (ref "C71") (pin "2") (pinfunction "2_2") (pintype "passive"))
      (node (ref "C72") (pin "2") (pinfunction "2_2") (pintype "passive"))
      (node (ref "ETHERNET") (pin "4") (pinfunction "GND1_4") (pintype "bidirectional"))
      (node (ref "ETHERNET") (pin "5") (pinfunction "GND2_5") (pintype "bidirectional"))
      (node (ref "IC4") (pin "11") (pinfunction "AGND_11") (pintype "power_in"))
      (node (ref "L1") (pin "1") (pinfunction "1_1") (pintype "passive"))
      (node (ref "STMF401") (pin "12") (pinfunction "VSSA_12") (pintype "power_in"))
      (node (ref "SYS-C2") (pin "2") (pinfunction "2_2") (pintype "passive"))
      (node (ref "U$4") (pin "29") (pinfunction "AGND_29") (pintype "power_in"))
    )
    (net (code "13") (name "CC_GPIO0") (class "Default")
      (node (ref "STMF401") (pin "5") (pinfunction "PH0_-OSC_IN_5") (pintype "bidirectional"))
      (node (ref "U$4") (pin "10") (pinfunction "GPIO0_10") (pintype "output"))
    )
    (net (code "14") (name "CC_GPIO1") (class "Default")
      (node (ref "STMF401") (pin "40") (pinfunction "PC9_40") (pintype "bidirectional"))
      (node (ref "U$4") (pin "9") (pinfunction "GPIO1_9") (pintype "output"))
    )
    (net (code "15") (name "CC_GPIO2") (class "Default")
      (node (ref "STMF401") (pin "39") (pinfunction "PC8_39") (pintype "bidirectional"))
      (node (ref "U$4") (pin "7") (pinfunction "GPIO2_7") (pintype "bidirectional"))
    )
    (net (code "16") (name "CC_GPIO3") (class "Default")
      (node (ref "STMF401") (pin "38") (pinfunction "PC7_38") (pintype "bidirectional"))
      (node (ref "U$4") (pin "6") (pinfunction "GPIO3_6") (pintype "bidirectional"))
    )
    (net (code "17") (name "CC_GPIO4") (class "Default")
      (node (ref "STMF401") (pin "15") (pinfunction "PA1_15") (pintype "bidirectional"))
      (node (ref "U$4") (pin "5") (pinfunction "GPIO4_5") (pintype "bidirectional"))
    )
    (net (code "18") (name "CC_GPIO5") (class "Default")
      (node (ref "STMF401") (pin "14") (pinfunction "PA0-WKUP1_14") (pintype "bidirectional"))
      (node (ref "U$4") (pin "4") (pinfunction "GPIO5_4") (pintype "bidirectional"))
    )
    (net (code "19") (name "CC_MISO") (class "Default")
      (node (ref "STMF401") (pin "52") (pinfunction "PC11_52") (pintype "bidirectional"))
      (node (ref "U$4") (pin "1") (pinfunction "SO_1") (pintype "output"))
    )
    (net (code "20") (name "CC_MOSI") (class "Default")
      (node (ref "STMF401") (pin "2") (pinfunction "PC13-RTC_AF1-WKUP2_2") (pintype "bidirectional"))
      (node (ref "U$4") (pin "2") (pinfunction "SI_2") (pintype "input"))
    )
    (net (code "21") (name "CC_RESET") (class "Default")
      (node (ref "U$4") (pin "25") (pinfunction "RESET_25") (pintype "input"))
    )
    (net (code "22") (name "CC_SCK") (class "Default")
      (node (ref "STMF401") (pin "53") (pinfunction "PC12_53") (pintype "bidirectional"))
      (node (ref "U$4") (pin "28") (pinfunction "SCLK_28") (pintype "input"))
    )
    (net (code "23") (name "CH1_A") (class "Default")
      (node (ref "JP1") (pin "1") (pinfunction "1_1") (pintype "passive"))
      (node (ref "OK2") (pin "8") (pinfunction "COL_8") (pintype "passive"))
    )
    (net (code "24") (name "CH1_B") (class "Default")
      (node (ref "JP1") (pin "2") (pinfunction "2_2") (pintype "passive"))
      (node (ref "OK2") (pin "7") (pinfunction "EMIT_7") (pintype "passive"))
    )
    (net (code "25") (name "CH1_IN") (class "Default")
      (node (ref "IC5") (pin "15") (pinfunction "QA_15") (pintype "tri_state"))
      (node (ref "OK2") (pin "2") (pinfunction "C_2") (pintype "passive"))
    )
    (net (code "26") (name "CH2_A") (class "Default")
      (node (ref "JP1") (pin "3") (pinfunction "3_3") (pintype "passive"))
      (node (ref "OK2") (pin "6") (pinfunction "COL_6") (pintype "passive"))
    )
    (net (code "27") (name "CH2_B") (class "Default")
      (node (ref "JP1") (pin "4") (pinfunction "4_4") (pintype "passive"))
      (node (ref "OK2") (pin "5") (pinfunction "EMIT_5") (pintype "passive"))
    )
    (net (code "28") (name "CH2_IN") (class "Default")
      (node (ref "IC5") (pin "1") (pinfunction "QB_1") (pintype "tri_state"))
      (node (ref "OK2") (pin "4") (pinfunction "C_4") (pintype "passive"))
    )
    (net (code "29") (name "CH3_A") (class "Default")
      (node (ref "JP1") (pin "5") (pinfunction "5_5") (pintype "passive"))
      (node (ref "OK1") (pin "8") (pinfunction "COL_8") (pintype "passive"))
    )
    (net (code "30") (name "CH3_B") (class "Default")
      (node (ref "JP1") (pin "6") (pinfunction "6_6") (pintype "passive"))
      (node (ref "OK1") (pin "7") (pinfunction "EMIT_7") (pintype "passive"))
    )
    (net (code "31") (name "CH3_IN") (class "Default")
      (node (ref "IC5") (pin "2") (pinfunction "QC_2") (pintype "tri_state"))
      (node (ref "OK1") (pin "2") (pinfunction "C_2") (pintype "passive"))
    )
    (net (code "32") (name "CH4_A") (class "Default")
      (node (ref "JP1") (pin "7") (pinfunction "7_7") (pintype "passive"))
      (node (ref "OK1") (pin "6") (pinfunction "COL_6") (pintype "passive"))
    )
    (net (code "33") (name "CH4_B") (class "Default")
      (node (ref "JP1") (pin "8") (pinfunction "8_8") (pintype "passive"))
      (node (ref "OK1") (pin "5") (pinfunction "EMIT_5") (pintype "passive"))
    )
    (net (code "34") (name "CH4_IN") (class "Default")
      (node (ref "IC5") (pin "3") (pinfunction "QD_3") (pintype "tri_state"))
      (node (ref "OK1") (pin "4") (pinfunction "C_4") (pintype "passive"))
    )
    (net (code "35") (name "DC_VOUT") (class "Default")
      (node (ref "DCDC") (pin "VOUT") (pinfunction "VOUT_VOUT") (pintype "bidirectional"))
      (node (ref "PWR") (pin "2") (pinfunction "2_2") (pintype "passive"))
    )
    (net (code "36") (name "DGND") (class "Default")
      (node (ref "ADE-C5") (pin "-") (pinfunction "-_-") (pintype "passive"))
      (node (ref "ANT1") (pin "P$1") (pinfunction "GND_P$1") (pintype "bidirectional"))
      (node (ref "ANT1") (pin "P$2") (pinfunction "GND_P$2") (pintype "bidirectional"))
      (node (ref "ANT2") (pin "P$1") (pinfunction "GND_P$1") (pintype "bidirectional"))
      (node (ref "ANT2") (pin "P$2") (pinfunction "GND_P$2") (pintype "bidirectional"))
      (node (ref "B1") (pin "2") (pinfunction "GND_2") (pintype "bidirectional"))
      (node (ref "B1") (pin "5") (pinfunction "GND_5") (pintype "bidirectional"))
      (node (ref "B1") (pin "6") (pinfunction "GND_6") (pintype "bidirectional"))
      (node (ref "BAT1") (pin "GND") (pinfunction "-_GND") (pintype "power_in"))
      (node (ref "C10") (pin "2") (pinfunction "2_2") (pintype "passive"))
      (node (ref "C20") (pin "2") (pinfunction "2_2") (pintype "passive"))
      (node (ref "C21") (pin "1") (pinfunction "1_1") (pintype "passive"))
      (node (ref "C22") (pin "1") (pinfunction "1_1") (pintype "passive"))
      (node (ref "C23") (pin "1") (pinfunction "1_1") (pintype "passive"))
      (node (ref "C24") (pin "2") (pinfunction "2_2") (pintype "passive"))
      (node (ref "C26") (pin "2") (pinfunction "2_2") (pintype "passive"))
      (node (ref "C27") (pin "2") (pinfunction "2_2") (pintype "passive"))
      (node (ref "C28") (pin "2") (pinfunction "2_2") (pintype "passive"))
      (node (ref "C30") (pin "1") (pinfunction "1_1") (pintype "passive"))
      (node (ref "C31") (pin "2") (pinfunction "2_2") (pintype "passive"))
      (node (ref "C33") (pin "2") (pinfunction "2_2") (pintype "passive"))
      (node (ref "C35") (pin "2") (pinfunction "2_2") (pintype "passive"))
      (node (ref "C36") (pin "1") (pinfunction "1_1") (pintype "passive"))
      (node (ref "C37") (pin "-") (pinfunction "-_-") (pintype "passive"))
      (node (ref "C40") (pin "2") (pinfunction "2_2") (pintype "passive"))
      (node (ref "C41") (pin "2") (pinfunction "2_2") (pintype "passive"))
      (node (ref "C43") (pin "2") (pinfunction "2_2") (pintype "passive"))
      (node (ref "C44") (pin "2") (pinfunction "2_2") (pintype "passive"))
      (node (ref "C45") (pin "2") (pinfunction "2_2") (pintype "passive"))
      (node (ref "C46") (pin "2") (pinfunction "2_2") (pintype "passive"))
      (node (ref "C50") (pin "2") (pinfunction "2_2") (pintype "passive"))
      (node (ref "C51") (pin "2") (pinfunction "2_2") (pintype "passive"))
      (node (ref "C52") (pin "2") (pinfunction "2_2") (pintype "passive"))
      (node (ref "C53") (pin "2") (pinfunction "2_2") (pintype "passive"))
      (node (ref "C54") (pin "2") (pinfunction "2_2") (pintype "passive"))
      (node (ref "C55") (pin "2") (pinfunction "2_2") (pintype "passive"))
      (node (ref "C56") (pin "2") (pinfunction "2_2") (pintype "passive"))
      (node (ref "C57") (pin "2") (pinfunction "2_2") (pintype "passive"))
      (node (ref "C70") (pin "2") (pinfunction "2_2") (pintype "passive"))
      (node (ref "C73") (pin "2") (pinfunction "2_2") (pintype "passive"))
      (node (ref "C74") (pin "2") (pinfunction "2_2") (pintype "passive"))
      (node (ref "C80") (pin "1") (pinfunction "1_1") (pintype "passive"))
      (node (ref "C81") (pin "1") (pinfunction "1_1") (pintype "passive"))
      (node (ref "C96") (pin "-") (pinfunction "-_-") (pintype "passive"))
      (node (ref "C97") (pin "-") (pinfunction "-_-") (pintype "passive"))
      (node (ref "DCDC") (pin "GND$1") (pinfunction "GNDI_GND$1") (pintype "bidirectional"))
      (node (ref "DCDC") (pin "GND$2") (pinfunction "GNDO_GND$2") (pintype "bidirectional"))
      (node (ref "ESP") (pin "GND") (pinfunction "GND_GND") (pintype "bidirectional"))
      (node (ref "ESP") (pin "GPIO15") (pinfunction "GPIO15_GPIO15") (pintype "bidirectional"))
      (node (ref "ESP-C1") (pin "2") (pinfunction "2_2") (pintype "passive"))
      (node (ref "ESP-GPIO0") (pin "3") (pinfunction "3_3") (pintype "passive"))
      (node (ref "HLK-PM01") (pin "GND") (pinfunction "GND_GND") (pintype "bidirectional"))
      (node (ref "IC1") (pin "P$17") (pinfunction "GND_P$17") (pintype "power_in"))
      (node (ref "IC1") (pin "P$18") (pinfunction "GND_P$18") (pintype "power_in"))
      (node (ref "IC1") (pin "P$29") (pinfunction "GND_P$29") (pintype "power_in"))
      (node (ref "IC1") (pin "P$39") (pinfunction "GND_P$39") (pintype "power_in"))
      (node (ref "IC1") (pin "P$45") (pinfunction "GND_P$45") (pintype "power_in"))
      (node (ref "IC1") (pin "P$46") (pinfunction "GND_P$46") (pintype "power_in"))
      (node (ref "IC1") (pin "P$53") (pinfunction "GND_P$53") (pintype "power_in"))
      (node (ref "IC1") (pin "P$54") (pinfunction "GND_P$54") (pintype "power_in"))
      (node (ref "IC1") (pin "P$58") (pinfunction "GND_P$58") (pintype "power_in"))
      (node (ref "IC1") (pin "P$59") (pinfunction "GND_P$59") (pintype "power_in"))
      (node (ref "IC1") (pin "P$61") (pinfunction "GND_P$61") (pintype "power_in"))
      (node (ref "IC1") (pin "P$62") (pinfunction "GND_P$62") (pintype "power_in"))
      (node (ref "IC1") (pin "P$63") (pinfunction "GND_P$63") (pintype "power_in"))
      (node (ref "IC1") (pin "P$64") (pinfunction "GND_P$64") (pintype "power_in"))
      (node (ref "IC1") (pin "P$65") (pinfunction "GND_P$65") (pintype "power_in"))
      (node (ref "IC2") (pin "13") (pinfunction "G_13") (pintype "input"))
      (node (ref "IC2") (pin "8") (pinfunction "GND_8") (pintype "power_in"))
      (node (ref "IC3") (pin "13") (pinfunction "G_13") (pintype "input"))
      (node (ref "IC3") (pin "8") (pinfunction "GND_8") (pintype "power_in"))
      (node (ref "IC4") (pin "2") (pinfunction "DGND_2") (pintype "power_in"))
      (node (ref "IC4") (pin "21") (pinfunction "CS_21") (pintype "input"))
      (node (ref "IC5") (pin "13") (pinfunction "G_13") (pintype "input"))
      (node (ref "IC5") (pin "8") (pinfunction "GND_8") (pintype "power_in"))
      (node (ref "L1") (pin "2") (pinfunction "2_2") (pintype "passive"))
      (node (ref "LCD14") (pin "LCD_GND") (pinfunction "LCD_GND_LCD_GND") (pintype "power_in"))
      (node (ref "LCD14") (pin "T_CS") (pinfunction "T_CS_T_CS") (pintype "bidirectional"))
      (node (ref "LCD_C1") (pin "2") (pinfunction "2_2") (pintype "passive"))
      (node (ref "MQ2-R1") (pin "1") (pinfunction "1_1") (pintype "passive"))
      (node (ref "R31") (pin "1") (pinfunction "1_1") (pintype "passive"))
      (node (ref "R50") (pin "1") (pinfunction "1_1") (pintype "passive"))
      (node (ref "R52") (pin "5") (pinfunction "2_5") (pintype "passive"))
      (node (ref "R52") (pin "6") (pinfunction "2_6") (pintype "passive"))
      (node (ref "R52") (pin "7") (pinfunction "2_7") (pintype "passive"))
      (node (ref "R52") (pin "8") (pinfunction "2_8") (pintype "passive"))
      (node (ref "R53") (pin "1") (pinfunction "1_1") (pintype "passive"))
      (node (ref "R90") (pin "2") (pinfunction "2_2") (pintype "passive"))
      (node (ref "R96") (pin "2") (pinfunction "2_2") (pintype "passive"))
      (node (ref "RBIAS") (pin "2") (pinfunction "2_2") (pintype "passive"))
      (node (ref "RJ-1") (pin "SHIELD$1") (pinfunction "P$5_SHIELD$1") (pintype "bidirectional"))
      (node (ref "RJ-2") (pin "SHIELD$1") (pinfunction "P$5_SHIELD$1") (pintype "bidirectional"))
      (node (ref "RJ-3") (pin "SHIELD$1") (pinfunction "P$5_SHIELD$1") (pintype "bidirectional"))
      (node (ref "S1") (pin "3") (pinfunction "3_3") (pintype "passive"))
      (node (ref "S1") (pin "4") (pinfunction "4_4") (pintype "passive"))
      (node (ref "SENSOR-MQ2") (pin "HB") (pinfunction "HB_HB") (pintype "bidirectional"))
      (node (ref "SIM900-C3") (pin "2") (pinfunction "2_2") (pintype "passive"))
      (node (ref "SIM900-C4") (pin "2") (pinfunction "2_2") (pintype "passive"))
      (node (ref "SIM900-C5") (pin "2") (pinfunction "2_2") (pintype "passive"))
      (node (ref "SIMHOLDER") (pin "SHIELD_GND$1") (pinfunction "GND$1_SHIELD_GND$1") (pintype "bidirectional"))
      (node (ref "SIMHOLDER") (pin "SHIELD_GND$2") (pinfunction "GND$2_SHIELD_GND$2") (pintype "bidirectional"))
      (node (ref "SIMHOLDER") (pin "SIM_GND") (pinfunction "SIM_GND_SIM_GND") (pintype "bidirectional"))
      (node (ref "SR_OUT1") (pin "2") (pinfunction "2_2") (pintype "passive"))
      (node (ref "SR_OUT2") (pin "2") (pinfunction "2_2") (pintype "passive"))
      (node (ref "STM-C13") (pin "2") (pinfunction "2_2") (pintype "passive"))
      (node (ref "STM-SWD") (pin "3") (pinfunction "3_3") (pintype "passive"))
      (node (ref "STM-USART") (pin "4") (pinfunction "4_4") (pintype "passive"))
      (node (ref "STMF401") (pin "18") (pinfunction "VSS_4_18") (pintype "power_in"))
      (node (ref "STMF401") (pin "31") (pinfunction "VSS_1_31") (pintype "power_in"))
      (node (ref "STMF401") (pin "47") (pinfunction "VSS_2_47") (pintype "power_in"))
      (node (ref "STMF401") (pin "63") (pinfunction "VSS_3_63") (pintype "power_in"))
      (node (ref "SYS-C1") (pin "2") (pinfunction "2_2") (pintype "passive"))
      (node (ref "T1") (pin "E") (pinfunction "E_E") (pintype "passive"))
      (node (ref "T2") (pin "E") (pinfunction "E_E") (pintype "passive"))
      (node (ref "T3") (pin "E") (pinfunction "E_E") (pintype "passive"))
      (node (ref "U$17") (pin "GND") (pinfunction "GND_GND") (pintype "bidirectional"))
      (node (ref "U$4") (pin "3") (pinfunction "CS_3") (pintype "input"))
      (node (ref "U2") (pin "14") (pinfunction "AGND_14") (pintype "passive"))
      (node (ref "U2") (pin "16") (pinfunction "AGND_16") (pintype "passive"))
      (node (ref "U2") (pin "19") (pinfunction "AGND_19") (pintype "passive"))
      (node (ref "U2") (pin "29") (pinfunction "GND_29") (pintype "passive"))
      (node (ref "U2") (pin "3") (pinfunction "AGND_3") (pintype "passive"))
      (node (ref "U2") (pin "48") (pinfunction "AGND_48") (pintype "passive"))
      (node (ref "U2") (pin "9") (pinfunction "AGND_9") (pintype "passive"))
      (node (ref "USB_IN") (pin "GND1") (pinfunction "GND_GND1") (pintype "bidirectional"))
      (node (ref "USB_IN") (pin "SHIELD1") (pinfunction "SHIELD_SHIELD1") (pintype "bidirectional"))
      (node (ref "USB_IN") (pin "SHIELD2") (pinfunction "SHIELD_SHIELD2") (pintype "bidirectional"))
      (node (ref "USB_IN") (pin "SHIELD3") (pinfunction "SHIELD_SHIELD3") (pintype "bidirectional"))
      (node (ref "W5500-C13") (pin "-") (pinfunction "-_-") (pintype "passive"))
    )
    (net (code "37") (name "DHT_DATA") (class "Default")
      (node (ref "DHT-R1") (pin "2") (pinfunction "2_2") (pintype "passive"))
      (node (ref "STMF401") (pin "54") (pinfunction "PD2_54") (pintype "bidirectional"))
      (node (ref "U$17") (pin "DATA") (pinfunction "DATA_DATA") (pintype "bidirectional"))
    )
    (net (code "38") (name "ESP_GPIO0") (class "Default")
      (node (ref "ESP") (pin "GPIO00") (pinfunction "GPIO0_GPIO00") (pintype "bidirectional"))
      (node (ref "ESP-GPIO0") (pin "2") (pinfunction "2_2") (pintype "passive"))
    )
    (net (code "39") (name "ESP_RX") (class "Default")
      (node (ref "ESP") (pin "RXD") (pinfunction "RXD_RXD") (pintype "bidirectional"))
      (node (ref "ESP_EXT") (pin "3") (pinfunction "3_3") (pintype "passive"))
      (node (ref "JRX") (pin "1") (pinfunction "1_1") (pintype "passive"))
    )
    (net (code "40") (name "ESP_TX") (class "Default")
      (node (ref "ESP") (pin "TXD") (pinfunction "TXD_TXD") (pintype "bidirectional"))
      (node (ref "ESP_EXT") (pin "4") (pinfunction "4_4") (pintype "passive"))
      (node (ref "JTX") (pin "1") (pinfunction "1_1") (pintype "passive"))
    )
    (net (code "41") (name "ETH_CS") (class "Default")
      (node (ref "R54") (pin "1") (pinfunction "1_1") (pintype "passive"))
      (node (ref "STMF401") (pin "33") (pinfunction "PB12_33") (pintype "bidirectional"))
      (node (ref "U2") (pin "32") (pinfunction "SCS_N_32") (pintype "passive"))
    )
    (net (code "42") (name "ETH_MISO") (class "Default")
      (node (ref "STMF401") (pin "35") (pinfunction "PB14_35") (pintype "bidirectional"))
      (node (ref "U2") (pin "34") (pinfunction "MISO_34") (pintype "passive"))
    )
    (net (code "43") (name "ETH_MOSI") (class "Default")
      (node (ref "STMF401") (pin "36") (pinfunction "PB15_36") (pintype "bidirectional"))
      (node (ref "U2") (pin "35") (pinfunction "MOSI_35") (pintype "passive"))
    )
    (net (code "44") (name "ETH_RSTN") (class "Default")
      (node (ref "R51") (pin "2") (pinfunction "2_2") (pintype "passive"))
      (node (ref "STMF401") (pin "37") (pinfunction "PC6_37") (pintype "bidirectional"))
      (node (ref "U2") (pin "37") (pinfunction "RST_N_37") (pintype "passive"))
    )
    (net (code "45") (name "ETH_SCK") (class "Default")
      (node (ref "STMF401") (pin "34") (pinfunction "PB13_34") (pintype "bidirectional"))
      (node (ref "U2") (pin "33") (pinfunction "SCLK_33") (pintype "passive"))
    )
    (net (code "46") (name "LCD_CS") (class "Default")
      (node (ref "LCD14") (pin "LCD_CS") (pinfunction "LCD_CS_LCD_CS") (pintype "bidirectional"))
      (node (ref "STMF401") (pin "20") (pinfunction "PA4_20") (pintype "bidirectional"))
    )
    (net (code "47") (name "LCD_D{slash}C") (class "Default")
      (node (ref "LCD14") (pin "LCD_D/C") (pinfunction "LCD_D/C_LCD_D/C") (pintype "bidirectional"))
      (node (ref "STMF401") (pin "24") (pinfunction "PC4_24") (pintype "bidirectional"))
    )
    (net (code "48") (name "LCD_MISO") (class "Default")
      (node (ref "LCD14") (pin "LCD_MISO") (pinfunction "LCD_MISO_LCD_MISO") (pintype "bidirectional"))
      (node (ref "LCD14") (pin "SD_MISO") (pinfunction "SD_MISO_SD_MISO") (pintype "bidirectional"))
      (node (ref "STMF401") (pin "22") (pinfunction "PA6_22") (pintype "bidirectional"))
    )
    (net (code "49") (name "LCD_MOSI") (class "Default")
      (node (ref "LCD14") (pin "LCD_MOSI") (pinfunction "LCD_MOSI_LCD_MOSI") (pintype "bidirectional"))
      (node (ref "LCD14") (pin "SD_MOSI") (pinfunction "SD_MOSI_SD_MOSI") (pintype "bidirectional"))
      (node (ref "STMF401") (pin "23") (pinfunction "PA7_23") (pintype "bidirectional"))
    )
    (net (code "50") (name "LCD_RESET") (class "Default")
      (node (ref "LCD14") (pin "LCD_RESET") (pinfunction "LCD_RESET_LCD_RESET") (pintype "bidirectional"))
      (node (ref "STMF401") (pin "25") (pinfunction "PC5_25") (pintype "bidirectional"))
    )
    (net (code "51") (name "LCD_SCK") (class "Default")
      (node (ref "LCD14") (pin "LCD_SCK") (pinfunction "LCD_SCK_LCD_SCK") (pintype "bidirectional"))
      (node (ref "LCD14") (pin "SD_SCK") (pinfunction "SD_SCK_SD_SCK") (pintype "bidirectional"))
      (node (ref "STMF401") (pin "21") (pinfunction "PA5_21") (pintype "bidirectional"))
    )
    (net (code "52") (name "LINKLED") (class "Default")
      (node (ref "ETH-R5") (pin "1") (pinfunction "1_1") (pintype "passive"))
      (node (ref "U2") (pin "25") (pinfunction "LINKLED_25") (pintype "passive"))
    )
    (net (code "53") (name "MQ2_DATA") (class "Default")
      (node (ref "MQ2-R1") (pin "2") (pinfunction "2_2") (pintype "passive"))
      (node (ref "SENSOR-MQ2") (pin "B1") (pinfunction "B1_B1") (pintype "bidirectional"))
      (node (ref "SENSOR-MQ2") (pin "B2") (pinfunction "B2_B2") (pintype "bidirectional"))
      (node (ref "STMF401") (pin "6") (pinfunction "PH1-_OSC_OUT_6") (pintype "bidirectional"))
    )
    (net (code "54") (name "N") (class "Default")
      (node (ref "HLK-PM01") (pin "AC$2") (pinfunction "AC_IN$2_AC$2") (pintype "bidirectional"))
      (node (ref "TERM_BLOCK") (pin "PIN$4") (pinfunction "P$4_PIN$4") (pintype "bidirectional"))
      (node (ref "TV16-1") (pin "IB") (pinfunction "IB_IB") (pintype "bidirectional"))
      (node (ref "TV16-2") (pin "IB") (pinfunction "IB_IB") (pintype "bidirectional"))
      (node (ref "TV16-3") (pin "IB") (pinfunction "IB_IB") (pintype "bidirectional"))
    )
    (net (code "55") (name "Net-(ADE-R1-Pad1)") (class "Default")
      (node (ref "ADE-R1") (pin "1") (pinfunction "1_1") (pintype "passive"))
      (node (ref "RTO1") (pin "2") (pinfunction "2_2") (pintype "passive"))
      (node (ref "TV16-1") (pin "OA") (pinfunction "OA_OA") (pintype "bidirectional"))
    )
    (net (code "56") (name "Net-(ADE-R2-Pad1)") (class "Default")
      (node (ref "ADE-R2") (pin "1") (pinfunction "1_1") (pintype "passive"))
      (node (ref "RTO2") (pin "2") (pinfunction "2_2") (pintype "passive"))
      (node (ref "TV16-2") (pin "OA") (pinfunction "OA_OA") (pintype "bidirectional"))
    )
    (net (code "57") (name "Net-(ADE-R3-Pad1)") (class "Default")
      (node (ref "ADE-R3") (pin "1") (pinfunction "1_1") (pintype "passive"))
      (node (ref "RTO3") (pin "2") (pinfunction "2_2") (pintype "passive"))
      (node (ref "TV16-3") (pin "OA") (pinfunction "OA_OA") (pintype "bidirectional"))
    )
    (net (code "58") (name "Net-(ADE-R7-Pad1)") (class "Default")
      (node (ref "ADE-R7") (pin "1") (pinfunction "1_1") (pintype "passive"))
      (node (ref "RTO1") (pin "1") (pinfunction "1_1") (pintype "passive"))
      (node (ref "RTO2") (pin "1") (pinfunction "1_1") (pintype "passive"))
      (node (ref "RTO3") (pin "1") (pinfunction "1_1") (pintype "passive"))
      (node (ref "TV16-1") (pin "OB") (pinfunction "OB_OB") (pintype "bidirectional"))
      (node (ref "TV16-2") (pin "OB") (pinfunction "OB_OB") (pintype "bidirectional"))
      (node (ref "TV16-3") (pin "OB") (pinfunction "OB_OB") (pintype "bidirectional"))
    )
    (net (code "59") (name "Net-(ADE-R8-Pad2)") (class "Default")
      (node (ref "ADE-R8") (pin "2") (pinfunction "2_2") (pintype "passive"))
      (node (ref "ADE-R9") (pin "1") (pinfunction "1_1") (pintype "passive"))
      (node (ref "RJ-3") (pin "P$3") (pinfunction "P$3_P$3") (pintype "bidirectional"))
      (node (ref "RJ-3") (pin "P$4") (pinfunction "P$4_P$4") (pintype "bidirectional"))
    )
    (net (code "60") (name "Net-(ADE-R10-Pad1)") (class "Default")
      (node (ref "ADE-R10") (pin "1") (pinfunction "1_1") (pintype "passive"))
      (node (ref "ADE-R8") (pin "1") (pinfunction "1_1") (pintype "passive"))
      (node (ref "RJ-3") (pin "P$1") (pinfunction "P$1_P$1") (pintype "bidirectional"))
      (node (ref "RJ-3") (pin "P$2") (pinfunction "P$2_P$2") (pintype "bidirectional"))
    )
    (net (code "61") (name "Net-(ADE-R11-Pad1)") (class "Default")
      (node (ref "ADE-R11") (pin "1") (pinfunction "1_1") (pintype "passive"))
      (node (ref "ADE-R13") (pin "1") (pinfunction "1_1") (pintype "passive"))
      (node (ref "RJ-2") (pin "P$1") (pinfunction "P$1_P$1") (pintype "bidirectional"))
      (node (ref "RJ-2") (pin "P$2") (pinfunction "P$2_P$2") (pintype "bidirectional"))
    )
    (net (code "62") (name "Net-(ADE-R11-Pad2)") (class "Default")
      (node (ref "ADE-R11") (pin "2") (pinfunction "2_2") (pintype "passive"))
      (node (ref "ADE-R12") (pin "1") (pinfunction "1_1") (pintype "passive"))
      (node (ref "RJ-2") (pin "P$3") (pinfunction "P$3_P$3") (pintype "bidirectional"))
      (node (ref "RJ-2") (pin "P$4") (pinfunction "P$4_P$4") (pintype "bidirectional"))
    )
    (net (code "63") (name "Net-(ADE-R14-Pad1)") (class "Default")
      (node (ref "ADE-R14") (pin "1") (pinfunction "1_1") (pintype "passive"))
      (node (ref "ADE-R16") (pin "1") (pinfunction "1_1") (pintype "passive"))
      (node (ref "RJ-1") (pin "P$1") (pinfunction "P$1_P$1") (pintype "bidirectional"))
      (node (ref "RJ-1") (pin "P$2") (pinfunction "P$2_P$2") (pintype "bidirectional"))
    )
    (net (code "64") (name "Net-(ADE-R14-Pad2)") (class "Default")
      (node (ref "ADE-R14") (pin "2") (pinfunction "2_2") (pintype "passive"))
      (node (ref "ADE-R15") (pin "1") (pinfunction "1_1") (pintype "passive"))
      (node (ref "RJ-1") (pin "P$3") (pinfunction "P$3_P$3") (pintype "bidirectional"))
      (node (ref "RJ-1") (pin "P$4") (pinfunction "P$4_P$4") (pintype "bidirectional"))
    )
    (net (code "65") (name "Net-(ANT1-SIGNAL)") (class "Default")
      (node (ref "ANT1") (pin "P$3") (pinfunction "SIGNAL_P$3") (pintype "bidirectional"))
      (node (ref "IC1") (pin "P$60") (pinfunction "RF_ANT_P$60") (pintype "bidirectional"))
    )
    (net (code "66") (name "Net-(ANT2-SIGNAL)") (class "Default")
      (node (ref "ANT2") (pin "P$3") (pinfunction "SIGNAL_P$3") (pintype "bidirectional"))
      (node (ref "B1") (pin "1") (pinfunction "ANT_1") (pintype "bidirectional"))
    )
    (net (code "67") (name "Net-(B1-BAL_N)") (class "Default")
      (node (ref "B1") (pin "3") (pinfunction "BAL_N_3") (pintype "bidirectional"))
      (node (ref "U$4") (pin "19") (pinfunction "RF-N_19") (pintype "bidirectional"))
    )
    (net (code "68") (name "Net-(B1-BAL_P)") (class "Default")
      (node (ref "B1") (pin "4") (pinfunction "BAL_P_4") (pintype "bidirectional"))
      (node (ref "U$4") (pin "17") (pinfunction "RF-P_17") (pintype "bidirectional"))
    )
    (net (code "69") (name "Net-(ETHERNET-LED1_K)") (class "Default")
      (node (ref "ETH-R4") (pin "2") (pinfunction "2_2") (pintype "passive"))
      (node (ref "ETHERNET") (pin "10") (pinfunction "LED1_K_10") (pintype "bidirectional"))
    )
    (net (code "70") (name "Net-(ETHERNET-LED2_K)") (class "Default")
      (node (ref "ETH-R5") (pin "2") (pinfunction "2_2") (pintype "passive"))
      (node (ref "ETHERNET") (pin "11") (pinfunction "LED2_K_11") (pintype "bidirectional"))
    )
    (net (code "71") (name "Net-(ETHERNET-RCT)") (class "Default")
      (node (ref "C30") (pin "2") (pinfunction "2_2") (pintype "passive"))
      (node (ref "ETHERNET") (pin "6") (pinfunction "RCT_6") (pintype "bidirectional"))
      (node (ref "R30") (pin "1") (pinfunction "1_1") (pintype "passive"))
      (node (ref "R32") (pin "2") (pinfunction "2_2") (pintype "passive"))
    )
    (net (code "72") (name "Net-(ETHERNET-RX+)") (class "Default")
      (node (ref "C32") (pin "1") (pinfunction "1_1") (pintype "passive"))
      (node (ref "ETHERNET") (pin "7") (pinfunction "RX+_7") (pintype "bidirectional"))
    )
    (net (code "73") (name "Net-(ETHERNET-RX-)") (class "Default")
      (node (ref "C34") (pin "1") (pinfunction "1_1") (pintype "passive"))
      (node (ref "ETHERNET") (pin "8") (pinfunction "RX-_8") (pintype "bidirectional"))
    )
    (net (code "74") (name "Net-(ETHERNET-TCT)") (class "Default")
      (node (ref "C36") (pin "2") (pinfunction "2_2") (pintype "passive"))
      (node (ref "ETHERNET") (pin "3") (pinfunction "TCT_3") (pintype "bidirectional"))
      (node (ref "R33") (pin "1") (pinfunction "1_1") (pintype "passive"))
    )
    (net (code "75") (name "Net-(HLK-PM01-PadVOUT)") (class "Default")
      (node (ref "HLK-PM01") (pin "VOUT") (pinfunction "VOUT_VOUT") (pintype "bidirectional"))
      (node (ref "S2") (pin "P$1") (pinfunction "P$1_P$1") (pintype "bidirectional"))
      (node (ref "S2") (pin "P$4") (pinfunction "P$4_P$4") (pintype "bidirectional"))
    )
    (net (code "76") (name "Net-(IC1-SIM_CLK)") (class "Default")
      (node (ref "IC1") (pin "P$32") (pinfunction "SIM_CLK_P$32") (pintype "bidirectional"))
      (node (ref "SIM900-R2") (pin "1") (pinfunction "1_1") (pintype "passive"))
    )
    (net (code "77") (name "Net-(IC1-SIM_DATA)") (class "Default")
      (node (ref "IC1") (pin "P$31") (pinfunction "SIM_DATA_P$31") (pintype "bidirectional"))
      (node (ref "SIM900-R3") (pin "1") (pinfunction "1_1") (pintype "passive"))
    )
    (net (code "78") (name "Net-(IC1-SIM_RST)") (class "Default")
      (node (ref "IC1") (pin "P$33") (pinfunction "SIM_RST_P$33") (pintype "bidirectional"))
      (node (ref "SIM900-R1") (pin "1") (pinfunction "1_1") (pintype "passive"))
    )
    (net (code "79") (name "Net-(IC1-VBAT1)") (class "Default")
      (node (ref "C96") (pin "+") (pinfunction "+_+") (pintype "passive"))
      (node (ref "C97") (pin "+") (pinfunction "+_+") (pintype "passive"))
      (node (ref "IC1") (pin "P$55") (pinfunction "VBAT1_P$55") (pintype "power_in"))
      (node (ref "IC1") (pin "P$56") (pinfunction "VBAT2_P$56") (pintype "power_in"))
      (node (ref "IC1") (pin "P$57") (pinfunction "VBAT3_P$57") (pintype "power_in"))
      (node (ref "L2") (pin "1") (pinfunction "1_1") (pintype "passive"))
    )
    (net (code "80") (name "Net-(IC1-VRTC)") (class "Default")
      (node (ref "IC1") (pin "P$26") (pinfunction "VRTC_P$26") (pintype "power_in"))
      (node (ref "SIM900-C3") (pin "1") (pinfunction "1_1") (pintype "passive"))
    )
    (net (code "81") (name "Net-(IC4A-CLKIN)") (class "Default")
      (node (ref "ADE-XTAL") (pin "1") (pinfunction "1_1") (pintype "passive"))
      (node (ref "C73") (pin "1") (pinfunction "1_1") (pintype "passive"))
      (node (ref "IC4") (pin "19") (pinfunction "CLKIN_19") (pintype "input"))
    )
    (net (code "82") (name "Net-(IC4A-CLKOUT)") (class "Default")
      (node (ref "ADE-XTAL") (pin "2") (pinfunction "2_2") (pintype "passive"))
      (node (ref "C74") (pin "1") (pinfunction "1_1") (pintype "passive"))
      (node (ref "IC4") (pin "20") (pinfunction "CLKOUT_20") (pintype "output"))
    )
    (net (code "83") (name "Net-(IC4C-IN)") (class "Default")
      (node (ref "ADE-C12") (pin "1") (pinfunction "1_1") (pintype "passive"))
      (node (ref "ADE-R10") (pin "2") (pinfunction "2_2") (pintype "passive"))
      (node (ref "IC4") (pin "6") (pinfunction "IN_6") (pintype "input"))
    )
    (net (code "84") (name "Net-(IC4C-IP)") (class "Default")
      (node (ref "ADE-C11") (pin "1") (pinfunction "1_1") (pintype "passive"))
      (node (ref "ADE-R9") (pin "2") (pinfunction "2_2") (pintype "passive"))
      (node (ref "IC4") (pin "5") (pinfunction "IP_5") (pintype "input"))
    )
    (net (code "85") (name "Net-(IC4D-IN)") (class "Default")
      (node (ref "ADE-C14") (pin "1") (pinfunction "1_1") (pintype "passive"))
      (node (ref "ADE-R13") (pin "2") (pinfunction "2_2") (pintype "passive"))
      (node (ref "IC4") (pin "8") (pinfunction "IN_8") (pintype "input"))
    )
    (net (code "86") (name "Net-(IC4D-IP)") (class "Default")
      (node (ref "ADE-C13") (pin "1") (pinfunction "1_1") (pintype "passive"))
      (node (ref "ADE-R12") (pin "2") (pinfunction "2_2") (pintype "passive"))
      (node (ref "IC4") (pin "7") (pinfunction "IP_7") (pintype "input"))
    )
    (net (code "87") (name "Net-(IC4E-IN)") (class "Default")
      (node (ref "ADE-C16") (pin "1") (pinfunction "1_1") (pintype "passive"))
      (node (ref "ADE-R16") (pin "2") (pinfunction "2_2") (pintype "passive"))
      (node (ref "IC4") (pin "10") (pinfunction "IN_10") (pintype "input"))
    )
    (net (code "88") (name "Net-(IC4E-IP)") (class "Default")
      (node (ref "ADE-C15") (pin "1") (pinfunction "1_1") (pintype "passive"))
      (node (ref "ADE-R15") (pin "2") (pinfunction "2_2") (pintype "passive"))
      (node (ref "IC4") (pin "9") (pinfunction "IP_9") (pintype "input"))
    )
    (net (code "89") (name "Net-(IC4F-REF)") (class "Default")
      (node (ref "C71") (pin "1") (pinfunction "1_1") (pintype "passive"))
      (node (ref "C72") (pin "1") (pinfunction "1_1") (pintype "passive"))
      (node (ref "IC4") (pin "12") (pinfunction "REF_12") (pintype "bidirectional"))
    )
    (net (code "90") (name "Net-(IC4G-VAP)") (class "Default")
      (node (ref "ADE-C7") (pin "1") (pinfunction "1_1") (pintype "passive"))
      (node (ref "ADE-R1") (pin "2") (pinfunction "2_2") (pintype "passive"))
      (node (ref "ADE-R4") (pin "2") (pinfunction "2_2") (pintype "passive"))
      (node (ref "IC4") (pin "16") (pinfunction "VAP_16") (pintype "input"))
    )
    (net (code "91") (name "Net-(IC4G-VBP)") (class "Default")
      (node (ref "ADE-C8") (pin "1") (pinfunction "1_1") (pintype "passive"))
      (node (ref "ADE-R2") (pin "2") (pinfunction "2_2") (pintype "passive"))
      (node (ref "ADE-R5") (pin "2") (pinfunction "2_2") (pintype "passive"))
      (node (ref "IC4") (pin "15") (pinfunction "VBP_15") (pintype "input"))
    )
    (net (code "92") (name "Net-(IC4G-VCP)") (class "Default")
      (node (ref "ADE-C9") (pin "1") (pinfunction "1_1") (pintype "passive"))
      (node (ref "ADE-R3") (pin "2") (pinfunction "2_2") (pintype "passive"))
      (node (ref "ADE-R6") (pin "2") (pinfunction "2_2") (pintype "passive"))
      (node (ref "IC4") (pin "14") (pinfunction "VCP_14") (pintype "input"))
    )
    (net (code "93") (name "Net-(IC4G-VN)") (class "Default")
      (node (ref "ADE-C10") (pin "1") (pinfunction "1_1") (pintype "passive"))
      (node (ref "ADE-R7") (pin "2") (pinfunction "2_2") (pintype "passive"))
      (node (ref "IC4") (pin "13") (pinfunction "VN_13") (pintype "input"))
    )
    (net (code "94") (name "Net-(LED1-PadA)") (class "Default")
      (node (ref "LED1") (pin "A") (pinfunction "A_A") (pintype "passive"))
      (node (ref "R94") (pin "1") (pinfunction "1_1") (pintype "passive"))
    )
    (net (code "95") (name "Net-(LED1-PadC)") (class "Default")
      (node (ref "LED1") (pin "C") (pinfunction "C_C") (pintype "passive"))
      (node (ref "T1") (pin "C") (pinfunction "C_C") (pintype "passive"))
    )
    (net (code "96") (name "Net-(LED2-PadA)") (class "Default")
      (node (ref "LED2") (pin "A") (pinfunction "A_A") (pintype "passive"))
      (node (ref "R92") (pin "1") (pinfunction "1_1") (pintype "passive"))
    )
    (net (code "97") (name "Net-(LED2-PadC)") (class "Default")
      (node (ref "LED2") (pin "C") (pinfunction "C_C") (pintype "passive"))
      (node (ref "T2") (pin "C") (pinfunction "C_C") (pintype "passive"))
    )
    (net (code "98") (name "Net-(OK1A-A)") (class "Default")
      (node (ref "OK1") (pin "1") (pinfunction "A_1") (pintype "passive"))
      (node (ref "R_CH3") (pin "2") (pinfunction "2_2") (pintype "passive"))
    )
    (net (code "99") (name "Net-(OK1B-A)") (class "Default")
      (node (ref "OK1") (pin "3") (pinfunction "A_3") (pintype "passive"))
      (node (ref "R_CH4") (pin "2") (pinfunction "2_2") (pintype "passive"))
    )
    (net (code "100") (name "Net-(OK2A-A)") (class "Default")
      (node (ref "OK2") (pin "1") (pinfunction "A_1") (pintype "passive"))
      (node (ref "R_CH1") (pin "2") (pinfunction "2_2") (pintype "passive"))
    )
    (net (code "101") (name "Net-(OK2B-A)") (class "Default")
      (node (ref "OK2") (pin "3") (pinfunction "A_3") (pintype "passive"))
      (node (ref "R_CH2") (pin "2") (pinfunction "2_2") (pintype "passive"))
    )
    (net (code "102") (name "Net-(R50-Pad2)") (class "Default")
      (node (ref "R50") (pin "2") (pinfunction "2_2") (pintype "passive"))
      (node (ref "U2") (pin "23") (pinfunction "RSVD_23") (pintype "passive"))
    )
    (net (code "103") (name "Net-(R52-Pad1)") (class "Default")
      (node (ref "R52") (pin "1") (pinfunction "1_1") (pintype "passive"))
      (node (ref "U2") (pin "41") (pinfunction "RSVD_41") (pintype "passive"))
    )
    (net (code "104") (name "Net-(R52B-1)") (class "Default")
      (node (ref "R52") (pin "2") (pinfunction "1_2") (pintype "passive"))
      (node (ref "U2") (pin "40") (pinfunction "RSVD_40") (pintype "passive"))
    )
    (net (code "105") (name "Net-(R52C-1)") (class "Default")
      (node (ref "R52") (pin "3") (pinfunction "1_3") (pintype "passive"))
      (node (ref "U2") (pin "39") (pinfunction "RSVD_39") (pintype "passive"))
    )
    (net (code "106") (name "Net-(R52D-1)") (class "Default")
      (node (ref "R52") (pin "4") (pinfunction "1_4") (pintype "passive"))
      (node (ref "U2") (pin "38") (pinfunction "RSVD_38") (pintype "passive"))
    )
    (net (code "107") (name "Net-(R53A-2)") (class "Default")
      (node (ref "R53") (pin "8") (pinfunction "2_8") (pintype "passive"))
      (node (ref "U2") (pin "42") (pinfunction "RSVD_42") (pintype "passive"))
    )
    (net (code "108") (name "Net-(R53B-2)") (class "Default")
      (node (ref "R53") (pin "7") (pinfunction "2_7") (pintype "passive"))
      (node (ref "U2") (pin "43") (pinfunction "PMODE2_43") (pintype "passive"))
    )
    (net (code "109") (name "Net-(R53C-2)") (class "Default")
      (node (ref "R53") (pin "6") (pinfunction "2_6") (pintype "passive"))
      (node (ref "U2") (pin "44") (pinfunction "PMODE1_44") (pintype "passive"))
    )
    (net (code "110") (name "Net-(R53D-2)") (class "Default")
      (node (ref "R53") (pin "5") (pinfunction "2_5") (pintype "passive"))
      (node (ref "U2") (pin "45") (pinfunction "PMODE0_45") (pintype "passive"))
    )
    (net (code "111") (name "Net-(R90-Pad1)") (class "Default")
      (node (ref "R90") (pin "1") (pinfunction "1_1") (pintype "passive"))
      (node (ref "R91") (pin "1") (pinfunction "1_1") (pintype "passive"))
      (node (ref "T2") (pin "B") (pinfunction "B_B") (pintype "passive"))
    )
    (net (code "112") (name "Net-(R93-Pad2)") (class "Default")
      (node (ref "R93") (pin "2") (pinfunction "2_2") (pintype "passive"))
      (node (ref "T3") (pin "B") (pinfunction "B_B") (pintype "passive"))
    )
    (net (code "113") (name "Net-(R95-Pad1)") (class "Default")
      (node (ref "R95") (pin "1") (pinfunction "1_1") (pintype "passive"))
      (node (ref "R96") (pin "1") (pinfunction "1_1") (pintype "passive"))
      (node (ref "T1") (pin "B") (pinfunction "B_B") (pintype "passive"))
    )
    (net (code "114") (name "Net-(RT1-Pad2)") (class "Default")
      (node (ref "RT1") (pin "2") (pinfunction "2_2") (pintype "passive"))
      (node (ref "TV16-1") (pin "IA") (pinfunction "IA_IA") (pintype "bidirectional"))
    )
    (net (code "115") (name "Net-(RT2-Pad2)") (class "Default")
      (node (ref "RT2") (pin "2") (pinfunction "2_2") (pintype "passive"))
      (node (ref "TV16-2") (pin "IA") (pinfunction "IA_IA") (pintype "bidirectional"))
    )
    (net (code "116") (name "Net-(RT3-Pad2)") (class "Default")
      (node (ref "RT3") (pin "2") (pinfunction "2_2") (pintype "passive"))
      (node (ref "TV16-3") (pin "IA") (pinfunction "IA_IA") (pintype "bidirectional"))
    )
    (net (code "117") (name "Net-(STMF401-PA2)") (class "Default")
      (node (ref "JRX") (pin "2") (pinfunction "2_2") (pintype "passive"))
      (node (ref "STMF401") (pin "16") (pinfunction "PA2_16") (pintype "bidirectional"))
    )
    (net (code "118") (name "Net-(STMF401-PA3)") (class "Default")
      (node (ref "JTX") (pin "2") (pinfunction "2_2") (pintype "passive"))
      (node (ref "STMF401") (pin "17") (pinfunction "PA3_17") (pintype "bidirectional"))
    )
    (net (code "119") (name "Net-(STMF401-PB11)") (class "Default")
      (node (ref "C28") (pin "1") (pinfunction "1_1") (pintype "passive"))
      (node (ref "STMF401") (pin "30") (pinfunction "PB11_30") (pintype "bidirectional"))
    )
    (net (code "120") (name "Net-(STMF401-PC14-OSC32_IN)") (class "Default")
      (node (ref "C22") (pin "2") (pinfunction "2_2") (pintype "passive"))
      (node (ref "STMF401") (pin "3") (pinfunction "PC14-OSC32_IN_3") (pintype "bidirectional"))
      (node (ref "XTAL1") (pin "2") (pinfunction "2_2") (pintype "passive"))
    )
    (net (code "121") (name "Net-(STMF401-PC15-OSC32_OUT)") (class "Default")
      (node (ref "C21") (pin "2") (pinfunction "2_2") (pintype "passive"))
      (node (ref "STMF401") (pin "4") (pinfunction "PC15-OSC32_OUT_4") (pintype "bidirectional"))
      (node (ref "XTAL1") (pin "1") (pinfunction "1_1") (pintype "passive"))
    )
    (net (code "122") (name "Net-(TERM_BLOCK-P$2)") (class "Default")
      (node (ref "RT2") (pin "1") (pinfunction "1_1") (pintype "passive"))
      (node (ref "TERM_BLOCK") (pin "PIN$2") (pinfunction "P$2_PIN$2") (pintype "bidirectional"))
    )
    (net (code "123") (name "Net-(TERM_BLOCK-P$3)") (class "Default")
      (node (ref "RT3") (pin "1") (pinfunction "1_1") (pintype "passive"))
      (node (ref "TERM_BLOCK") (pin "PIN$3") (pinfunction "P$3_PIN$3") (pintype "bidirectional"))
    )
    (net (code "124") (name "Net-(U$4B-DCOUPL)") (class "Default")
      (node (ref "C40") (pin "1") (pinfunction "1_1") (pintype "passive"))
      (node (ref "U$4") (pin "27") (pinfunction "DCOUPL_27") (pintype "power_in"))
    )
    (net (code "125") (name "Net-(U$4C-RBIAS)") (class "Default")
      (node (ref "RBIAS") (pin "1") (pinfunction "1_1") (pintype "passive"))
      (node (ref "U$4") (pin "23") (pinfunction "RBIAS_23") (pintype "bidirectional"))
    )
    (net (code "126") (name "Net-(U$4C-VREG-EN)") (class "Default")
      (node (ref "R_VREG") (pin "1") (pinfunction "1_1") (pintype "passive"))
      (node (ref "U$4") (pin "26") (pinfunction "VREG-EN_26") (pintype "input"))
    )
    (net (code "127") (name "Net-(U$4C-XOSC32M-Q1)") (class "Default")
      (node (ref "C44") (pin "1") (pinfunction "1_1") (pintype "passive"))
      (node (ref "U$4") (pin "13") (pinfunction "XOSC32M-Q1_13") (pintype "input"))
      (node (ref "X1") (pin "1") (pinfunction "1_1") (pintype "bidirectional"))
    )
    (net (code "128") (name "Net-(U$4C-XOSC32M-Q2)") (class "Default")
      (node (ref "C45") (pin "1") (pinfunction "1_1") (pintype "passive"))
      (node (ref "U$4") (pin "12") (pinfunction "XOSC32M-Q2_12") (pintype "output"))
      (node (ref "X1") (pin "3") (pinfunction "2_3") (pintype "bidirectional"))
    )
    (net (code "129") (name "Net-(U2-1V2O)") (class "Default")
      (node (ref "C55") (pin "1") (pinfunction "1_1") (pintype "passive"))
      (node (ref "U2") (pin "22") (pinfunction "1V2O_22") (pintype "passive"))
    )
    (net (code "130") (name "Net-(U2-EXRES1)") (class "Default")
      (node (ref "R31") (pin "2") (pinfunction "2_2") (pintype "passive"))
      (node (ref "U2") (pin "10") (pinfunction "EXRES1_10") (pintype "passive"))
    )
    (net (code "131") (name "Net-(U2-TOCAP)") (class "Default")
      (node (ref "C52") (pin "1") (pinfunction "1_1") (pintype "passive"))
      (node (ref "U2") (pin "20") (pinfunction "TOCAP_20") (pintype "passive"))
    )
    (net (code "132") (name "Net-(U2-XI{slash}CLKIN)") (class "Default")
      (node (ref "C54") (pin "1") (pinfunction "1_1") (pintype "passive"))
      (node (ref "R56") (pin "1") (pinfunction "1_1") (pintype "passive"))
      (node (ref "U2") (pin "30") (pinfunction "XI/CLKIN_30") (pintype "passive"))
      (node (ref "XTAL2") (pin "1") (pinfunction "1_1") (pintype "passive"))
    )
    (net (code "133") (name "Net-(U2-XO)") (class "Default")
      (node (ref "C57") (pin "1") (pinfunction "1_1") (pintype "passive"))
      (node (ref "R56") (pin "2") (pinfunction "2_2") (pintype "passive"))
      (node (ref "U2") (pin "31") (pinfunction "XO_31") (pintype "passive"))
      (node (ref "XTAL2") (pin "2") (pinfunction "2_2") (pintype "passive"))
    )
    (net (code "134") (name "Q1") (class "Default")
      (node (ref "IC2") (pin "15") (pinfunction "QA_15") (pintype "tri_state"))
      (node (ref "SR_OUT1") (pin "3") (pinfunction "3_3") (pintype "passive"))
    )
    (net (code "135") (name "Q2") (class "Default")
      (node (ref "IC2") (pin "1") (pinfunction "QB_1") (pintype "tri_state"))
      (node (ref "SR_OUT1") (pin "4") (pinfunction "4_4") (pintype "passive"))
    )
    (net (code "136") (name "Q3") (class "Default")
      (node (ref "IC2") (pin "2") (pinfunction "QC_2") (pintype "tri_state"))
      (node (ref "SR_OUT1") (pin "5") (pinfunction "5_5") (pintype "passive"))
    )
    (net (code "137") (name "Q4") (class "Default")
      (node (ref "IC2") (pin "3") (pinfunction "QD_3") (pintype "tri_state"))
      (node (ref "SR_OUT1") (pin "6") (pinfunction "6_6") (pintype "passive"))
    )
    (net (code "138") (name "Q5") (class "Default")
      (node (ref "IC2") (pin "4") (pinfunction "QE_4") (pintype "tri_state"))
      (node (ref "SR_OUT1") (pin "7") (pinfunction "7_7") (pintype "passive"))
    )
    (net (code "139") (name "Q6") (class "Default")
      (node (ref "IC2") (pin "5") (pinfunction "QF_5") (pintype "tri_state"))
      (node (ref "SR_OUT1") (pin "8") (pinfunction "8_8") (pintype "passive"))
    )
    (net (code "140") (name "Q7") (class "Default")
      (node (ref "IC2") (pin "6") (pinfunction "QG_6") (pintype "tri_state"))
      (node (ref "SR_OUT1") (pin "9") (pinfunction "9_9") (pintype "passive"))
    )
    (net (code "141") (name "Q8") (class "Default")
      (node (ref "IC2") (pin "7") (pinfunction "QH_7") (pintype "tri_state"))
      (node (ref "SR_OUT1") (pin "10") (pinfunction "10_10") (pintype "passive"))
    )
    (net (code "142") (name "Q9") (class "Default")
      (node (ref "IC3") (pin "15") (pinfunction "QA_15") (pintype "tri_state"))
      (node (ref "SR_OUT2") (pin "3") (pinfunction "3_3") (pintype "passive"))
    )
    (net (code "143") (name "Q10") (class "Default")
      (node (ref "IC3") (pin "1") (pinfunction "QB_1") (pintype "tri_state"))
      (node (ref "SR_OUT2") (pin "4") (pinfunction "4_4") (pintype "passive"))
    )
    (net (code "144") (name "Q11") (class "Default")
      (node (ref "IC3") (pin "2") (pinfunction "QC_2") (pintype "tri_state"))
      (node (ref "SR_OUT2") (pin "5") (pinfunction "5_5") (pintype "passive"))
    )
    (net (code "145") (name "Q12") (class "Default")
      (node (ref "IC3") (pin "3") (pinfunction "QD_3") (pintype "tri_state"))
      (node (ref "SR_OUT2") (pin "6") (pinfunction "6_6") (pintype "passive"))
    )
    (net (code "146") (name "Q13") (class "Default")
      (node (ref "IC3") (pin "4") (pinfunction "QE_4") (pintype "tri_state"))
      (node (ref "SR_OUT2") (pin "7") (pinfunction "7_7") (pintype "passive"))
    )
    (net (code "147") (name "Q14") (class "Default")
      (node (ref "IC3") (pin "5") (pinfunction "QF_5") (pintype "tri_state"))
      (node (ref "SR_OUT2") (pin "8") (pinfunction "8_8") (pintype "passive"))
    )
    (net (code "148") (name "Q15") (class "Default")
      (node (ref "IC3") (pin "6") (pinfunction "QG_6") (pintype "tri_state"))
      (node (ref "SR_OUT2") (pin "9") (pinfunction "9_9") (pintype "passive"))
    )
    (net (code "149") (name "Q16") (class "Default")
      (node (ref "IC3") (pin "7") (pinfunction "QH_7") (pintype "tri_state"))
      (node (ref "SR_OUT2") (pin "10") (pinfunction "10_10") (pintype "passive"))
    )
    (net (code "150") (name "QS") (class "Default")
      (node (ref "IC2") (pin "9") (pinfunction "QH*_9") (pintype "tri_state"))
      (node (ref "IC3") (pin "14") (pinfunction "SER_14") (pintype "input"))
    )
    (net (code "151") (name "QS2") (class "Default")
      (node (ref "IC3") (pin "9") (pinfunction "QH*_9") (pintype "tri_state"))
      (node (ref "IC5") (pin "14") (pinfunction "SER_14") (pintype "input"))
    )
    (net (code "152") (name "R") (class "Default")
      (node (ref "HLK-PM01") (pin "AC$1") (pinfunction "AC_IN$1_AC$1") (pintype "bidirectional"))
      (node (ref "RT1") (pin "1") (pinfunction "1_1") (pintype "passive"))
      (node (ref "TERM_BLOCK") (pin "PIN$1") (pinfunction "P$1_PIN$1") (pintype "bidirectional"))
    )
    (net (code "153") (name "RXN") (class "Default")
      (node (ref "C34") (pin "2") (pinfunction "2_2") (pintype "passive"))
      (node (ref "R32") (pin "1") (pinfunction "1_1") (pintype "passive"))
      (node (ref "U2") (pin "5") (pinfunction "RXN_5") (pintype "passive"))
    )
    (net (code "154") (name "RXP") (class "Default")
      (node (ref "C32") (pin "2") (pinfunction "2_2") (pintype "passive"))
      (node (ref "R30") (pin "2") (pinfunction "2_2") (pintype "passive"))
      (node (ref "U2") (pin "6") (pinfunction "RXP_6") (pintype "passive"))
    )
    (net (code "155") (name "SD_CS") (class "Default")
      (node (ref "LCD14") (pin "SD_CS") (pinfunction "SD_CS_SD_CS") (pintype "bidirectional"))
      (node (ref "STMF401") (pin "55") (pinfunction "PB3_55") (pintype "bidirectional"))
    )
    (net (code "156") (name "SERIAL_RX") (class "Default")
      (node (ref "STM-USART") (pin "3") (pinfunction "3_3") (pintype "passive"))
      (node (ref "STMF401") (pin "43") (pinfunction "PA10_43") (pintype "bidirectional"))
    )
    (net (code "157") (name "SERIAL_TX") (class "Default")
      (node (ref "STM-USART") (pin "2") (pinfunction "2_2") (pintype "passive"))
      (node (ref "STMF401") (pin "42") (pinfunction "PA9_42") (pintype "bidirectional"))
    )
    (net (code "158") (name "SIM900_PWRKEY") (class "Default")
      (node (ref "IC1") (pin "P$1") (pinfunction "PWRKEY_P$1") (pintype "power_in"))
      (node (ref "T3") (pin "C") (pinfunction "C_C") (pintype "passive"))
    )
    (net (code "159") (name "SIM_NETLIGHT") (class "Default")
      (node (ref "IC1") (pin "P$52") (pinfunction "NETLIGHT_P$52") (pintype "bidirectional"))
      (node (ref "R91") (pin "2") (pinfunction "2_2") (pintype "passive"))
    )
    (net (code "160") (name "SIM_PWRKEY") (class "Default")
      (node (ref "R93") (pin "1") (pinfunction "1_1") (pintype "passive"))
      (node (ref "STMF401") (pin "41") (pinfunction "PA8_41") (pintype "bidirectional"))
    )
    (net (code "161") (name "SIM_RX") (class "Default")
      (node (ref "IC1") (pin "P$10") (pinfunction "RXD_P$10") (pintype "input"))
      (node (ref "STMF401") (pin "51") (pinfunction "PC10_51") (pintype "bidirectional"))
    )
    (net (code "162") (name "SIM_STATUS") (class "Default")
      (node (ref "IC1") (pin "P$66") (pinfunction "STATUS_P$66") (pintype "bidirectional"))
      (node (ref "R95") (pin "2") (pinfunction "2_2") (pintype "passive"))
    )
    (net (code "163") (name "SIM_TX") (class "Default")
      (node (ref "IC1") (pin "P$9") (pinfunction "TXD_P$9") (pintype "output"))
      (node (ref "STMF401") (pin "50") (pinfunction "PA15_50") (pintype "bidirectional"))
    )
    (net (code "164") (name "SR_DS") (class "Default")
      (node (ref "IC2") (pin "14") (pinfunction "SER_14") (pintype "input"))
      (node (ref "STMF401") (pin "8") (pinfunction "PC0_8") (pintype "bidirectional"))
    )
    (net (code "165") (name "SR_RST") (class "Default")
      (node (ref "IC2") (pin "10") (pinfunction "SCL_10") (pintype "input"))
      (node (ref "IC3") (pin "10") (pinfunction "SCL_10") (pintype "input"))
      (node (ref "IC5") (pin "10") (pinfunction "SCL_10") (pintype "input"))
      (node (ref "STMF401") (pin "11") (pinfunction "PC3_11") (pintype "bidirectional"))
    )
    (net (code "166") (name "SR_SHCP") (class "Default")
      (node (ref "IC2") (pin "11") (pinfunction "SCK_11") (pintype "input"))
      (node (ref "IC3") (pin "11") (pinfunction "SCK_11") (pintype "input"))
      (node (ref "IC5") (pin "11") (pinfunction "SCK_11") (pintype "input"))
      (node (ref "STMF401") (pin "10") (pinfunction "PC2_10") (pintype "bidirectional"))
    )
    (net (code "167") (name "SR_STCP") (class "Default")
      (node (ref "IC2") (pin "12") (pinfunction "RCK_12") (pintype "input"))
      (node (ref "IC3") (pin "12") (pinfunction "RCK_12") (pintype "input"))
      (node (ref "IC5") (pin "12") (pinfunction "RCK_12") (pintype "input"))
      (node (ref "STMF401") (pin "9") (pinfunction "PC1_9") (pintype "bidirectional"))
    )
    (net (code "168") (name "SWD_NRST") (class "Default")
      (node (ref "C20") (pin "1") (pinfunction "1_1") (pintype "passive"))
      (node (ref "S1") (pin "1") (pinfunction "1_1") (pintype "passive"))
      (node (ref "S1") (pin "2") (pinfunction "2_2") (pintype "passive"))
      (node (ref "STMF401") (pin "7") (pinfunction "NRST_7") (pintype "bidirectional"))
    )
    (net (code "169") (name "SWD_TCK") (class "Default")
      (node (ref "STM-SWD") (pin "2") (pinfunction "2_2") (pintype "passive"))
      (node (ref "STMF401") (pin "49") (pinfunction "PA14_49") (pintype "bidirectional"))
    )
    (net (code "170") (name "SWD_TMS") (class "Default")
      (node (ref "STM-SWD") (pin "4") (pinfunction "4_4") (pintype "passive"))
      (node (ref "STMF401") (pin "46") (pinfunction "PA13_46") (pintype "bidirectional"))
    )
    (net (code "171") (name "TXN") (class "Default")
      (node (ref "ETHERNET") (pin "2") (pinfunction "TX-_2") (pintype "bidirectional"))
      (node (ref "R34") (pin "1") (pinfunction "1_1") (pintype "passive"))
      (node (ref "U2") (pin "1") (pinfunction "TXN_1") (pintype "passive"))
    )
    (net (code "172") (name "TXP") (class "Default")
      (node (ref "ETHERNET") (pin "1") (pinfunction "TX+_1") (pintype "bidirectional"))
      (node (ref "R35") (pin "1") (pinfunction "1_1") (pintype "passive"))
      (node (ref "U2") (pin "2") (pinfunction "TXP_2") (pintype "passive"))
    )
    (net (code "173") (name "T_CLK") (class "Default")
      (node (ref "LCD14") (pin "T_CLK") (pinfunction "T_CLK_T_CLK") (pintype "bidirectional"))
      (node (ref "STMF401") (pin "27") (pinfunction "PB1_27") (pintype "bidirectional"))
    )
    (net (code "174") (name "T_DIN") (class "Default")
      (node (ref "LCD14") (pin "T_DIN") (pinfunction "T_DIN_T_DIN") (pintype "bidirectional"))
      (node (ref "STMF401") (pin "29") (pinfunction "PB10_29") (pintype "bidirectional"))
    )
    (net (code "175") (name "T_DO") (class "Default")
      (node (ref "LCD14") (pin "T_DO") (pinfunction "T_DO_T_DO") (pintype "bidirectional"))
      (node (ref "STMF401") (pin "26") (pinfunction "PB0_26") (pintype "bidirectional"))
    )
    (net (code "176") (name "T_IRQ") (class "Default")
      (node (ref "LCD14") (pin "T_IRQ") (pinfunction "T_IRQ_T_IRQ") (pintype "bidirectional"))
      (node (ref "STMF401") (pin "28") (pinfunction "PB2_28") (pintype "bidirectional"))
    )
    (net (code "177") (name "USB_DM") (class "Default")
      (node (ref "STMF401") (pin "44") (pinfunction "PA11_44") (pintype "bidirectional"))
      (node (ref "USB_IN") (pin "D-1") (pinfunction "D-_D-1") (pintype "bidirectional"))
    )
    (net (code "178") (name "USB_DP") (class "Default")
      (node (ref "STMF401") (pin "45") (pinfunction "PA12_45") (pintype "bidirectional"))
      (node (ref "USB_IN") (pin "D+1") (pinfunction "D+_D+1") (pintype "bidirectional"))
    )
    (net (code "179") (name "USIM_CLK") (class "Default")
      (node (ref "SIM900-R2") (pin "2") (pinfunction "2_2") (pintype "passive"))
      (node (ref "SIMHOLDER") (pin "SIM_CLK") (pinfunction "SIM_CLK_SIM_CLK") (pintype "bidirectional"))
    )
    (net (code "180") (name "USIM_DATA") (class "Default")
      (node (ref "SIM900-R3") (pin "2") (pinfunction "2_2") (pintype "passive"))
      (node (ref "SIMHOLDER") (pin "SIM_IO") (pinfunction "SIM_IO_SIM_IO") (pintype "bidirectional"))
    )
    (net (code "181") (name "USIM_RESET") (class "Default")
      (node (ref "SIM900-R1") (pin "2") (pinfunction "2_2") (pintype "passive"))
      (node (ref "SIMHOLDER") (pin "SIM_RST") (pinfunction "SIM_RST_SIM_RST") (pintype "bidirectional"))
    )
    (net (code "182") (name "USIM_VCC") (class "Default")
      (node (ref "C80") (pin "2") (pinfunction "2_2") (pintype "passive"))
      (node (ref "C81") (pin "2") (pinfunction "2_2") (pintype "passive"))
      (node (ref "IC1") (pin "P$30") (pinfunction "SIM_VDD_P$30") (pintype "power_in"))
      (node (ref "SIM900-C4") (pin "1") (pinfunction "1_1") (pintype "passive"))
      (node (ref "SIM900-C5") (pin "1") (pinfunction "1_1") (pintype "passive"))
      (node (ref "SIMHOLDER") (pin "SIM_VDD") (pinfunction "SIM_VDD_SIM_VDD") (pintype "bidirectional"))
    )
    (net (code "183") (name "VBAT") (class "Default")
      (node (ref "BAT1") (pin "PWR@1") (pinfunction "+_PWR@1") (pintype "power_in"))
      (node (ref "STMF401") (pin "1") (pinfunction "VLCD_1") (pintype "power_in"))
    )
    (net (code "184") (name "VCC") (class "Default")
      (node (ref "C11") (pin "1") (pinfunction "1_1") (pintype "passive"))
      (node (ref "C25") (pin "1") (pinfunction "1_1") (pintype "passive"))
      (node (ref "C31") (pin "1") (pinfunction "1_1") (pintype "passive"))
      (node (ref "C33") (pin "1") (pinfunction "1_1") (pintype "passive"))
      (node (ref "C35") (pin "1") (pinfunction "1_1") (pintype "passive"))
      (node (ref "C37") (pin "+") (pinfunction "+_+") (pintype "passive"))
      (node (ref "C50") (pin "1") (pinfunction "1_1") (pintype "passive"))
      (node (ref "C51") (pin "1") (pinfunction "1_1") (pintype "passive"))
      (node (ref "C53") (pin "1") (pinfunction "1_1") (pintype "passive"))
      (node (ref "L3") (pin "2") (pinfunction "2_2") (pintype "passive"))
      (node (ref "R10") (pin "2") (pinfunction "2_2") (pintype "passive"))
      (node (ref "R33") (pin "2") (pinfunction "2_2") (pintype "passive"))
      (node (ref "R34") (pin "2") (pinfunction "2_2") (pintype "passive"))
      (node (ref "R35") (pin "2") (pinfunction "2_2") (pintype "passive"))
      (node (ref "STMF401") (pin "13") (pinfunction "VDDA_13") (pintype "power_in"))
      (node (ref "U2") (pin "11") (pinfunction "AVDD_11") (pintype "passive"))
      (node (ref "U2") (pin "15") (pinfunction "AVDD_15") (pintype "passive"))
      (node (ref "U2") (pin "17") (pinfunction "AVDD_17") (pintype "passive"))
      (node (ref "U2") (pin "21") (pinfunction "AVDD_21") (pintype "passive"))
      (node (ref "U2") (pin "4") (pinfunction "AVDD_4") (pintype "passive"))
      (node (ref "U2") (pin "8") (pinfunction "AVDD_8") (pintype "passive"))
    )
    (net (code "185") (name "VDD") (class "Default")
      (node (ref "C10") (pin "1") (pinfunction "1_1") (pintype "passive"))
      (node (ref "C23") (pin "2") (pinfunction "2_2") (pintype "passive"))
      (node (ref "C24") (pin "1") (pinfunction "1_1") (pintype "passive"))
      (node (ref "C26") (pin "1") (pinfunction "1_1") (pintype "passive"))
      (node (ref "C27") (pin "1") (pinfunction "1_1") (pintype "passive"))
      (node (ref "C41") (pin "1") (pinfunction "1_1") (pintype "passive"))
      (node (ref "C43") (pin "1") (pinfunction "1_1") (pintype "passive"))
      (node (ref "C46") (pin "1") (pinfunction "1_1") (pintype "passive"))
      (node (ref "C56") (pin "1") (pinfunction "1_1") (pintype "passive"))
      (node (ref "DHT-R1") (pin "1") (pinfunction "1_1") (pintype "passive"))
      (node (ref "ESP_EXT") (pin "1") (pinfunction "1_1") (pintype "passive"))
      (node (ref "ETHERNET") (pin "12") (pinfunction "LED2_A_12") (pintype "bidirectional"))
      (node (ref "ETHERNET") (pin "9") (pinfunction "LED1_A_9") (pintype "bidirectional"))
      (node (ref "IC2") (pin "16") (pinfunction "VCC_16") (pintype "power_in"))
      (node (ref "IC3") (pin "16") (pinfunction "VCC_16") (pintype "power_in"))
      (node (ref "IC5") (pin "16") (pinfunction "VCC_16") (pintype "power_in"))
      (node (ref "L2") (pin "2") (pinfunction "2_2") (pintype "passive"))
      (node (ref "L3") (pin "1") (pinfunction "1_1") (pintype "passive"))
      (node (ref "LCD14") (pin "LCD_VCC") (pinfunction "LCD_VCC_LCD_VCC") (pintype "power_in"))
      (node (ref "LCD14") (pin "LED") (pinfunction "LCD_LED_LED") (pintype "bidirectional"))
      (node (ref "LCD_C1") (pin "1") (pinfunction "1_1") (pintype "passive"))
      (node (ref "PWR") (pin "1") (pinfunction "1_1") (pintype "passive"))
      (node (ref "R10") (pin "1") (pinfunction "1_1") (pintype "passive"))
      (node (ref "R51") (pin "1") (pinfunction "1_1") (pintype "passive"))
      (node (ref "R53") (pin "2") (pinfunction "1_2") (pintype "passive"))
      (node (ref "R53") (pin "3") (pinfunction "1_3") (pintype "passive"))
      (node (ref "R53") (pin "4") (pinfunction "1_4") (pintype "passive"))
      (node (ref "R54") (pin "2") (pinfunction "2_2") (pintype "passive"))
      (node (ref "R92") (pin "2") (pinfunction "2_2") (pintype "passive"))
      (node (ref "R94") (pin "2") (pinfunction "2_2") (pintype "passive"))
      (node (ref "R_VREG") (pin "2") (pinfunction "2_2") (pintype "passive"))
      (node (ref "STM-C13") (pin "1") (pinfunction "1_1") (pintype "passive"))
      (node (ref "STM-SWD") (pin "1") (pinfunction "1_1") (pintype "passive"))
      (node (ref "STM-USART") (pin "1") (pinfunction "1_1") (pintype "passive"))
      (node (ref "STMF401") (pin "19") (pinfunction "VDD_4_19") (pintype "power_in"))
      (node (ref "STMF401") (pin "32") (pinfunction "VDD_1_32") (pintype "power_in"))
      (node (ref "STMF401") (pin "48") (pinfunction "VDD_2_48") (pintype "power_in"))
      (node (ref "STMF401") (pin "64") (pinfunction "VDD_3_64") (pintype "power_in"))
      (node (ref "U$17") (pin "VCC") (pinfunction "VCC_VCC") (pintype "bidirectional"))
      (node (ref "U$4") (pin "11") (pinfunction "AVDD_11") (pintype "power_in"))
      (node (ref "U$4") (pin "14") (pinfunction "AVDD_14") (pintype "power_in"))
      (node (ref "U$4") (pin "16") (pinfunction "AVDD_16") (pintype "power_in"))
      (node (ref "U$4") (pin "20") (pinfunction "AVDD_20") (pintype "power_in"))
      (node (ref "U$4") (pin "22") (pinfunction "AVDD_22") (pintype "power_in"))
      (node (ref "U$4") (pin "24") (pinfunction "AVDD-GUARD_24") (pintype "power_in"))
      (node (ref "U$4") (pin "8") (pinfunction "DVDD_8") (pintype "power_in"))
      (node (ref "U2") (pin "28") (pinfunction "VDD_28") (pintype "passive"))
      (node (ref "W5500-C13") (pin "+") (pinfunction "+_+") (pintype "passive"))
    )
    (net (code "186") (name "VESP") (class "Default")
      (node (ref "ESP") (pin "CH_PD") (pinfunction "CH_PD_CH_PD") (pintype "bidirectional"))
      (node (ref "ESP") (pin "GPIO02") (pinfunction "GPIO2_GPIO02") (pintype "bidirectional"))
      (node (ref "ESP") (pin "REST") (pinfunction "REST_REST") (pintype "bidirectional"))
      (node (ref "ESP") (pin "VCC") (pinfunction "VCC_VCC") (pintype "power_in"))
      (node (ref "ESP-C1") (pin "1") (pinfunction "1_1") (pintype "passive"))
      (node (ref "ESP-GPIO0") (pin "1") (pinfunction "1_1") (pintype "passive"))
      (node (ref "ESP_EXT") (pin "2") (pinfunction "2_2") (pintype "passive"))
    )
    (net (code "187") (name "unconnected-(ESP-GPIO4-PadGPIO04)") (class "Default")
      (node (ref "ESP") (pin "GPIO04") (pinfunction "GPIO4_GPIO04") (pintype "bidirectional"))
    )
    (net (code "188") (name "unconnected-(ESP-GPIO5-PadGPIO05)") (class "Default")
      (node (ref "ESP") (pin "GPIO05") (pinfunction "GPIO5_GPIO05") (pintype "bidirectional"))
    )
    (net (code "189") (name "unconnected-(ESP-PadADC)") (class "Default")
      (node (ref "ESP") (pin "ADC") (pinfunction "ADC_ADC") (pintype "bidirectional"))
    )
    (net (code "190") (name "unconnected-(ESP-PadGPIO12)") (class "Default")
      (node (ref "ESP") (pin "GPIO12") (pinfunction "GPIO12_GPIO12") (pintype "bidirectional"))
    )
    (net (code "191") (name "unconnected-(ESP-PadGPIO13)") (class "Default")
      (node (ref "ESP") (pin "GPIO13") (pinfunction "GPIO13_GPIO13") (pintype "bidirectional"))
    )
    (net (code "192") (name "unconnected-(ESP-PadGPIO14)") (class "Default")
      (node (ref "ESP") (pin "GPIO14") (pinfunction "GPIO14_GPIO14") (pintype "bidirectional"))
    )
    (net (code "193") (name "unconnected-(ESP-PadGPIO16)") (class "Default")
      (node (ref "ESP") (pin "GPIO16") (pinfunction "GPIO16_GPIO16") (pintype "bidirectional"))
    )
    (net (code "194") (name "unconnected-(IC1-ADC-PadP$25)") (class "Default")
      (node (ref "IC1") (pin "P$25") (pinfunction "ADC_P$25") (pintype "bidirectional"))
    )
    (net (code "195") (name "unconnected-(IC1-CTS-PadP$7)") (class "Default")
      (node (ref "IC1") (pin "P$7") (pinfunction "CTS_P$7") (pintype "output"))
    )
    (net (code "196") (name "unconnected-(IC1-DBG_RXD-PadP$28)") (class "Default")
      (node (ref "IC1") (pin "P$28") (pinfunction "DBG_RXD_P$28") (pintype "input"))
    )
    (net (code "197") (name "unconnected-(IC1-DBG_TXD-PadP$27)") (class "Default")
      (node (ref "IC1") (pin "P$27") (pinfunction "DBG_TXD_P$27") (pintype "output"))
    )
    (net (code "198") (name "unconnected-(IC1-DCD-PadP$5)") (class "Default")
      (node (ref "IC1") (pin "P$5") (pinfunction "DCD_P$5") (pintype "output"))
    )
    (net (code "199") (name "unconnected-(IC1-DISP_CLK-PadP$11)") (class "Default")
      (node (ref "IC1") (pin "P$11") (pinfunction "DISP_CLK_P$11") (pintype "bidirectional"))
    )
    (net (code "200") (name "unconnected-(IC1-DISP_CS-PadP$14)") (class "Default")
      (node (ref "IC1") (pin "P$14") (pinfunction "DISP_CS_P$14") (pintype "bidirectional"))
    )
    (net (code "201") (name "unconnected-(IC1-DISP_DATA-PadP$12)") (class "Default")
      (node (ref "IC1") (pin "P$12") (pinfunction "DISP_DATA_P$12") (pintype "bidirectional"))
    )
    (net (code "202") (name "unconnected-(IC1-DISP_DC-PadP$13)") (class "Default")
      (node (ref "IC1") (pin "P$13") (pinfunction "DISP_DC_P$13") (pintype "bidirectional"))
    )
    (net (code "203") (name "unconnected-(IC1-DTR-PadP$3)") (class "Default")
      (node (ref "IC1") (pin "P$3") (pinfunction "DTR_P$3") (pintype "input"))
    )
    (net (code "204") (name "unconnected-(IC1-GPIO1{slash}KBR4-PadP$40)") (class "Default")
      (node (ref "IC1") (pin "P$40") (pinfunction "GPIO1/KBR4_P$40") (pintype "bidirectional"))
    )
    (net (code "205") (name "unconnected-(IC1-GPIO2{slash}KBR3-PadP$41)") (class "Default")
      (node (ref "IC1") (pin "P$41") (pinfunction "GPIO2/KBR3_P$41") (pintype "bidirectional"))
    )
    (net (code "206") (name "unconnected-(IC1-GPIO3{slash}KBR2-PadP$42)") (class "Default")
      (node (ref "IC1") (pin "P$42") (pinfunction "GPIO3/KBR2_P$42") (pintype "bidirectional"))
    )
    (net (code "207") (name "unconnected-(IC1-GPIO4{slash}KBR1-PadP$43)") (class "Default")
      (node (ref "IC1") (pin "P$43") (pinfunction "GPIO4/KBR1_P$43") (pintype "bidirectional"))
    )
    (net (code "208") (name "unconnected-(IC1-GPIO5{slash}KBR0-PadP$44)") (class "Default")
      (node (ref "IC1") (pin "P$44") (pinfunction "GPIO5/KBR0_P$44") (pintype "bidirectional"))
    )
    (net (code "209") (name "unconnected-(IC1-GPIO6{slash}KBC4-PadP$47)") (class "Default")
      (node (ref "IC1") (pin "P$47") (pinfunction "GPIO6/KBC4_P$47") (pintype "bidirectional"))
    )
    (net (code "210") (name "unconnected-(IC1-GPIO7{slash}KBC3-PadP$48)") (class "Default")
      (node (ref "IC1") (pin "P$48") (pinfunction "GPIO7/KBC3_P$48") (pintype "bidirectional"))
    )
    (net (code "211") (name "unconnected-(IC1-GPIO8{slash}KBC2-PadP$49)") (class "Default")
      (node (ref "IC1") (pin "P$49") (pinfunction "GPIO8/KBC2_P$49") (pintype "bidirectional"))
    )
    (net (code "212") (name "unconnected-(IC1-GPIO9{slash}KBC1-PadP$50)") (class "Default")
      (node (ref "IC1") (pin "P$50") (pinfunction "GPIO9/KBC1_P$50") (pintype "bidirectional"))
    )
    (net (code "213") (name "unconnected-(IC1-GPIO10-PadP$51)") (class "Default")
      (node (ref "IC1") (pin "P$51") (pinfunction "GPIO10_P$51") (pintype "bidirectional"))
    )
    (net (code "214") (name "unconnected-(IC1-LINEIN_L-PadP$24)") (class "Default")
      (node (ref "IC1") (pin "P$24") (pinfunction "LINEIN_L_P$24") (pintype "bidirectional"))
    )
    (net (code "215") (name "unconnected-(IC1-LINEIN_R-PadP$23)") (class "Default")
      (node (ref "IC1") (pin "P$23") (pinfunction "LINEIN_R_P$23") (pintype "bidirectional"))
    )
    (net (code "216") (name "unconnected-(IC1-MIC_N-PadP$20)") (class "Default")
      (node (ref "IC1") (pin "P$20") (pinfunction "MIC_N_P$20") (pintype "bidirectional"))
    )
    (net (code "217") (name "unconnected-(IC1-MIC_P-PadP$19)") (class "Default")
      (node (ref "IC1") (pin "P$19") (pinfunction "MIC_P_P$19") (pintype "bidirectional"))
    )
    (net (code "218") (name "unconnected-(IC1-NC-PadP$2)") (class "Default")
      (node (ref "IC1") (pin "P$2") (pinfunction "NC_P$2") (pintype "no_connect"))
    )
    (net (code "219") (name "unconnected-(IC1-NC-PadP$6)") (class "Default")
      (node (ref "IC1") (pin "P$6") (pinfunction "NC_P$6") (pintype "no_connect"))
    )
    (net (code "220") (name "unconnected-(IC1-NRESET-PadP$16)") (class "Default")
      (node (ref "IC1") (pin "P$16") (pinfunction "NRESET_P$16") (pintype "bidirectional"))
    )
    (net (code "221") (name "unconnected-(IC1-PWM1-PadP$35)") (class "Default")
      (node (ref "IC1") (pin "P$35") (pinfunction "PWM1_P$35") (pintype "bidirectional"))
    )
    (net (code "222") (name "unconnected-(IC1-PWM2-PadP$36)") (class "Default")
      (node (ref "IC1") (pin "P$36") (pinfunction "PWM2_P$36") (pintype "bidirectional"))
    )
    (net (code "223") (name "unconnected-(IC1-RI-PadP$4)") (class "Default")
      (node (ref "IC1") (pin "P$4") (pinfunction "RI_P$4") (pintype "output"))
    )
    (net (code "224") (name "unconnected-(IC1-RTS-PadP$8)") (class "Default")
      (node (ref "IC1") (pin "P$8") (pinfunction "RTS_P$8") (pintype "input"))
    )
    (net (code "225") (name "unconnected-(IC1-SCL-PadP$38)") (class "Default")
      (node (ref "IC1") (pin "P$38") (pinfunction "SCL_P$38") (pintype "bidirectional"))
    )
    (net (code "226") (name "unconnected-(IC1-SDA-PadP$37)") (class "Default")
      (node (ref "IC1") (pin "P$37") (pinfunction "SDA_P$37") (pintype "bidirectional"))
    )
    (net (code "227") (name "unconnected-(IC1-SIM_PRESENCE-PadP$34)") (class "Default")
      (node (ref "IC1") (pin "P$34") (pinfunction "SIM_PRESENCE_P$34") (pintype "bidirectional"))
    )
    (net (code "228") (name "unconnected-(IC1-SPK_N-PadP$22)") (class "Default")
      (node (ref "IC1") (pin "P$22") (pinfunction "SPK_N_P$22") (pintype "bidirectional"))
    )
    (net (code "229") (name "unconnected-(IC1-SPK_P-PadP$21)") (class "Default")
      (node (ref "IC1") (pin "P$21") (pinfunction "SPK_P_P$21") (pintype "bidirectional"))
    )
    (net (code "230") (name "unconnected-(IC1-VDD_EXT-PadP$15)") (class "Default")
      (node (ref "IC1") (pin "P$15") (pinfunction "VDD_EXT_P$15") (pintype "bidirectional"))
    )
    (net (code "231") (name "unconnected-(IC5A-QE-Pad4)") (class "Default")
      (node (ref "IC5") (pin "4") (pinfunction "QE_4") (pintype "tri_state"))
    )
    (net (code "232") (name "unconnected-(IC5A-QF-Pad5)") (class "Default")
      (node (ref "IC5") (pin "5") (pinfunction "QF_5") (pintype "tri_state"))
    )
    (net (code "233") (name "unconnected-(IC5A-QG-Pad6)") (class "Default")
      (node (ref "IC5") (pin "6") (pinfunction "QG_6") (pintype "tri_state"))
    )
    (net (code "234") (name "unconnected-(IC5A-QH*-Pad9)") (class "Default")
      (node (ref "IC5") (pin "9") (pinfunction "QH*_9") (pintype "tri_state"))
    )
    (net (code "235") (name "unconnected-(IC5A-QH-Pad7)") (class "Default")
      (node (ref "IC5") (pin "7") (pinfunction "QH_7") (pintype "tri_state"))
    )
    (net (code "236") (name "unconnected-(S2-PadP$2)") (class "Default")
      (node (ref "S2") (pin "P$2") (pinfunction "P$2_P$2") (pintype "bidirectional"))
    )
    (net (code "237") (name "unconnected-(S2-PadP$5)") (class "Default")
      (node (ref "S2") (pin "P$5") (pinfunction "P$5_P$5") (pintype "bidirectional"))
    )
    (net (code "238") (name "unconnected-(SIMHOLDER-PadVPP)") (class "Default")
      (node (ref "SIMHOLDER") (pin "VPP") (pinfunction "VPP_VPP") (pintype "bidirectional"))
    )
    (net (code "239") (name "unconnected-(STMF401-BOOT0-Pad60)") (class "Default")
      (node (ref "STMF401") (pin "60") (pinfunction "BOOT0_60") (pintype "input"))
    )
    (net (code "240") (name "unconnected-(U$17-PadNO)") (class "Default")
      (node (ref "U$17") (pin "NO") (pinfunction "NO_NO") (pintype "bidirectional"))
    )
    (net (code "241") (name "unconnected-(U2-DNC-Pad7)") (class "Default")
      (node (ref "U2") (pin "7") (pinfunction "DNC_7") (pintype "passive"))
    )
    (net (code "242") (name "unconnected-(U2-DUPLED-Pad26)") (class "Default")
      (node (ref "U2") (pin "26") (pinfunction "DUPLED_26") (pintype "passive"))
    )
    (net (code "243") (name "unconnected-(U2-INT_N-Pad36)") (class "Default")
      (node (ref "U2") (pin "36") (pinfunction "INT_N_36") (pintype "passive"))
    )
    (net (code "244") (name "unconnected-(U2-NC-Pad12)") (class "Default")
      (node (ref "U2") (pin "12") (pinfunction "NC_12") (pintype "passive"))
    )
    (net (code "245") (name "unconnected-(U2-NC-Pad13)") (class "Default")
      (node (ref "U2") (pin "13") (pinfunction "NC_13") (pintype "passive"))
    )
    (net (code "246") (name "unconnected-(U2-NC-Pad46)") (class "Default")
      (node (ref "U2") (pin "46") (pinfunction "NC_46") (pintype "passive"))
    )
    (net (code "247") (name "unconnected-(U2-NC-Pad47)") (class "Default")
      (node (ref "U2") (pin "47") (pinfunction "NC_47") (pintype "passive"))
    )
    (net (code "248") (name "unconnected-(U2-SPDLED-Pad24)") (class "Default")
      (node (ref "U2") (pin "24") (pinfunction "SPDLED_24") (pintype "passive"))
    )
    (net (code "249") (name "unconnected-(U2-VBG-Pad18)") (class "Default")
      (node (ref "U2") (pin "18") (pinfunction "VBG_18") (pintype "passive"))
    )
    (net (code "250") (name "unconnected-(USB_IN-ID-PadID1)") (class "Default")
      (node (ref "USB_IN") (pin "ID1") (pinfunction "ID_ID1") (pintype "bidirectional"))
    )
  )
)
